# board2corrected.net
KiCad netlist of a schematic drawn in EAGLE
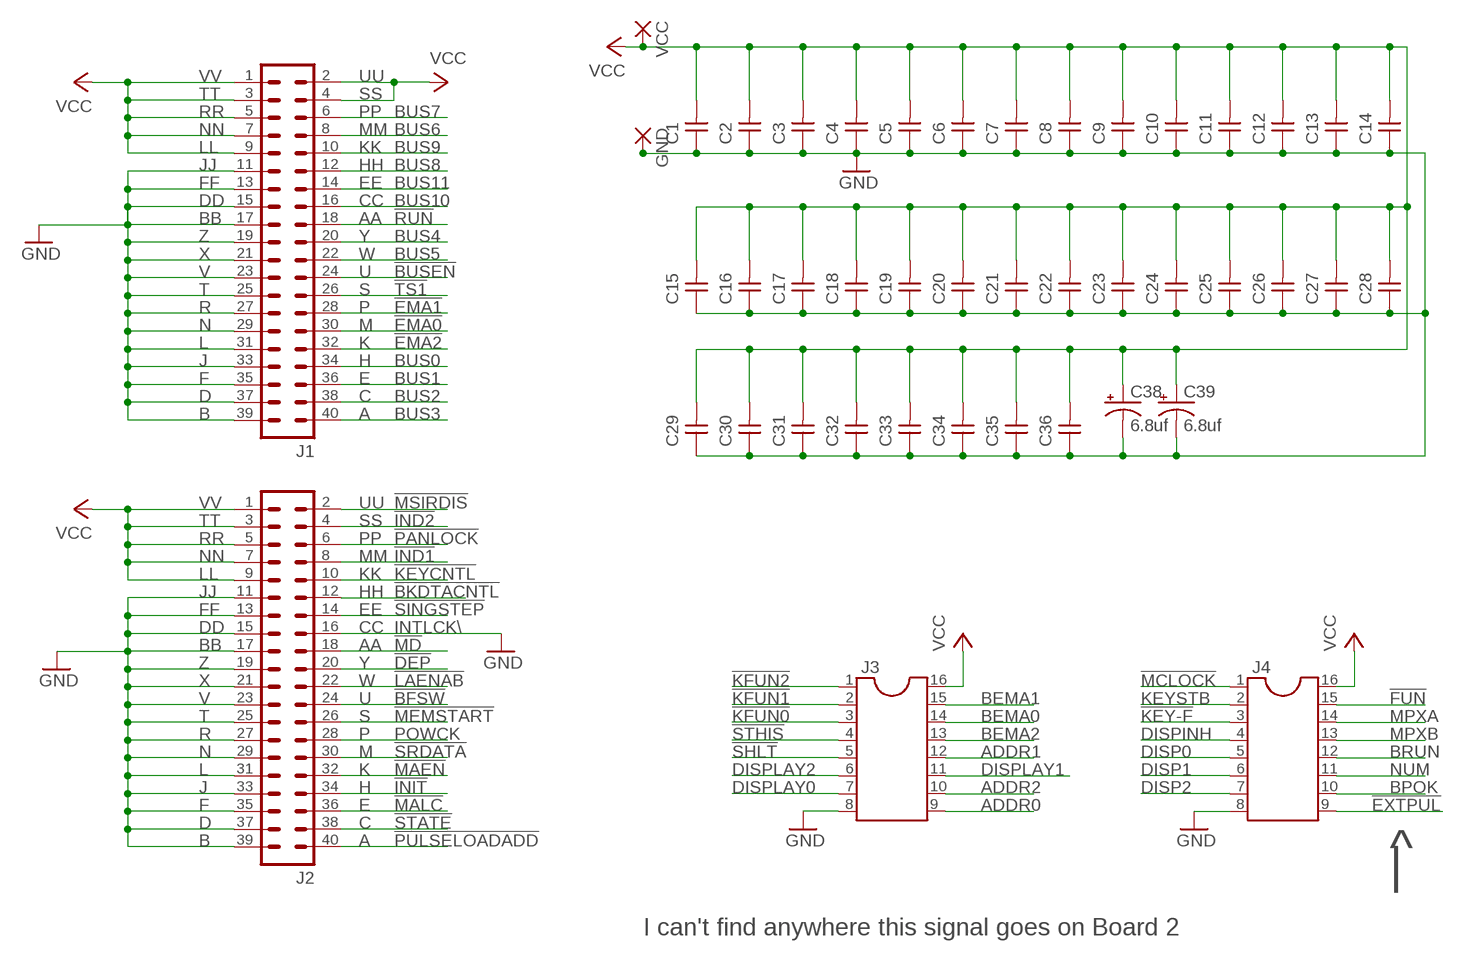
[diagram p0: schematic, sheet 1]
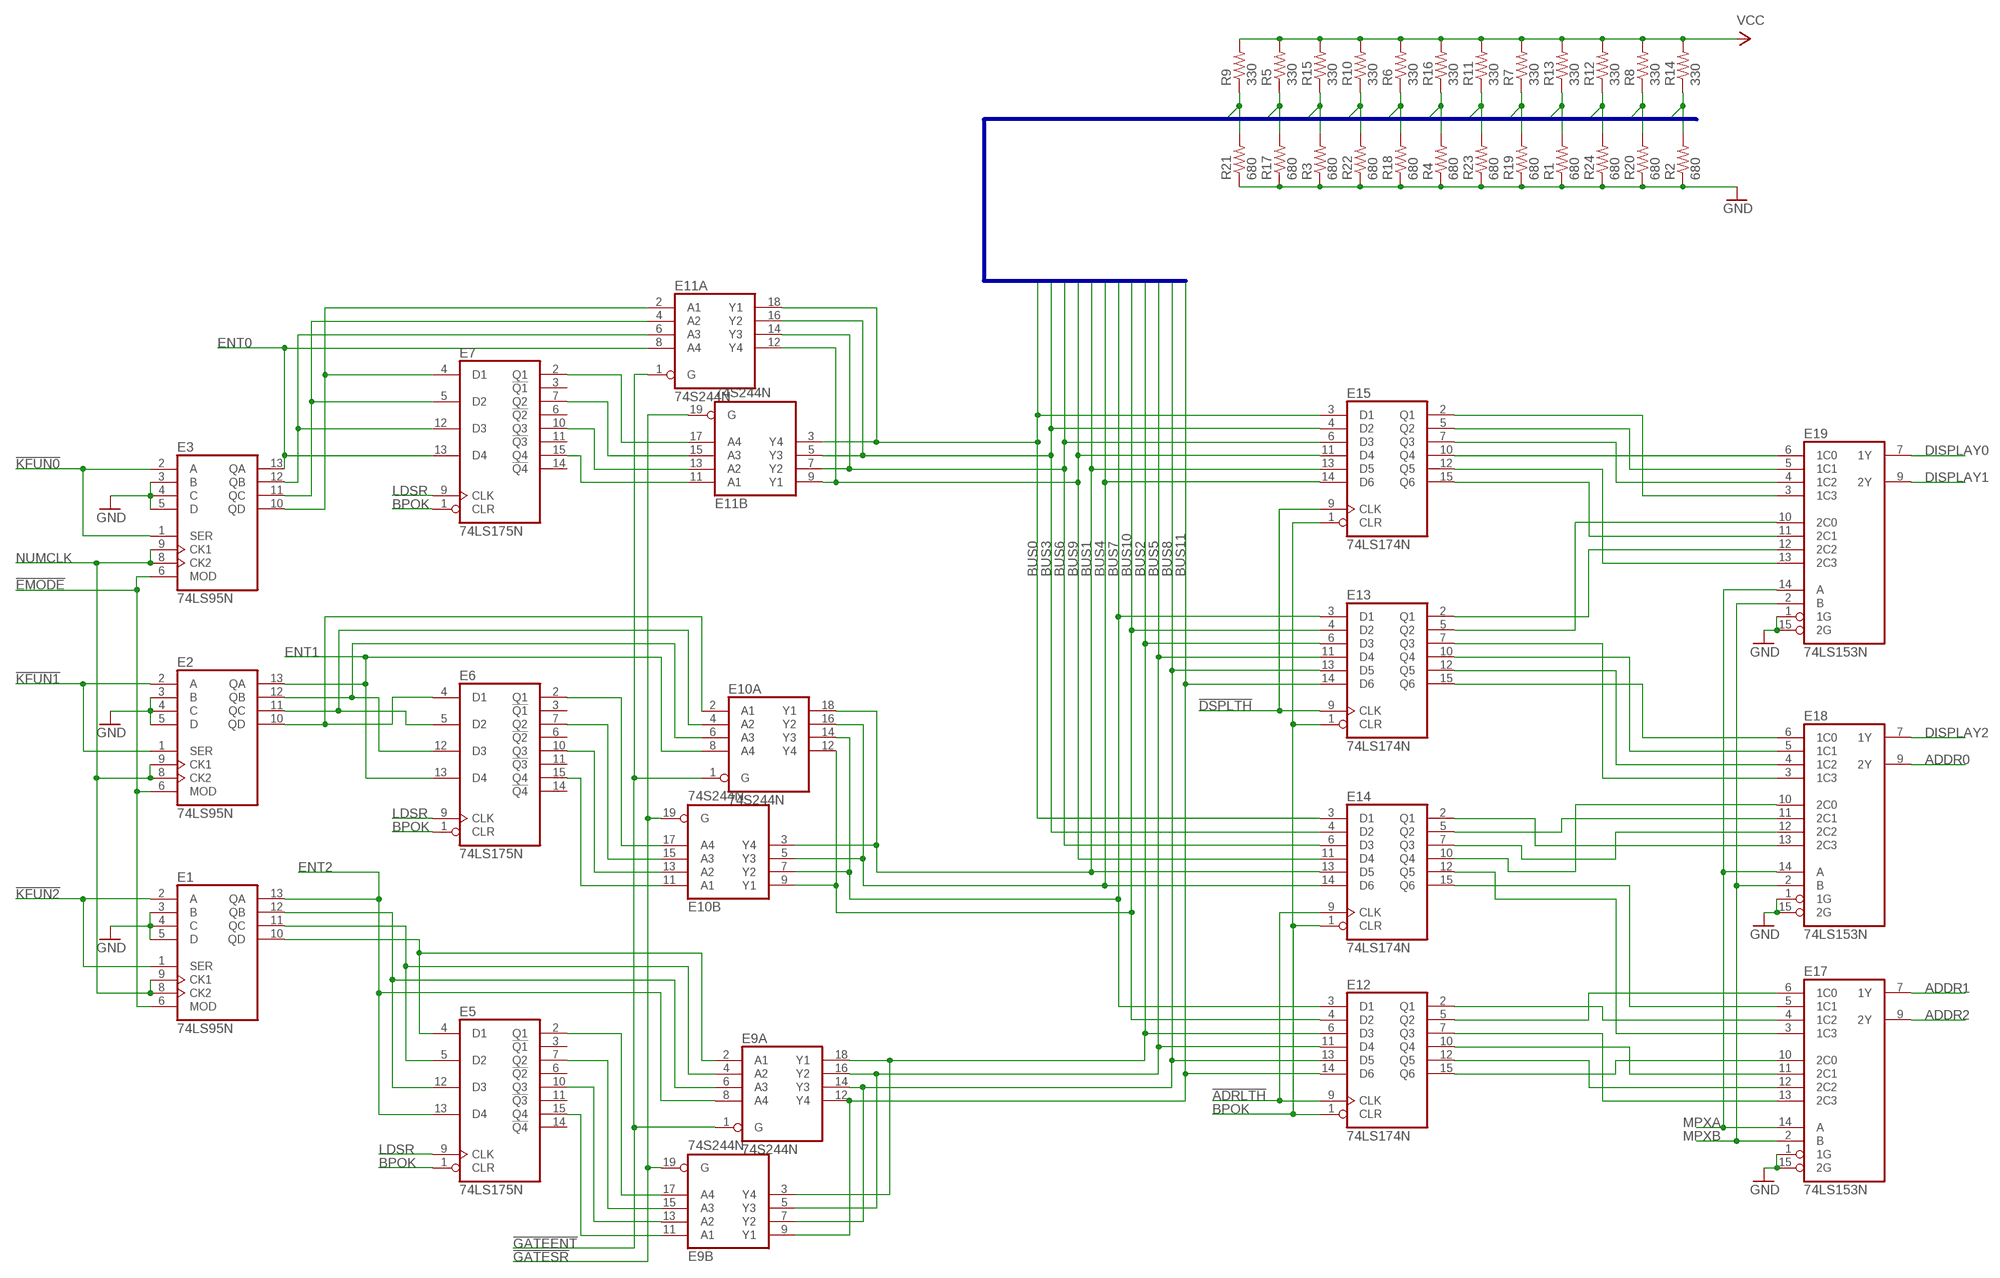
[diagram p1: schematic, sheet 2]
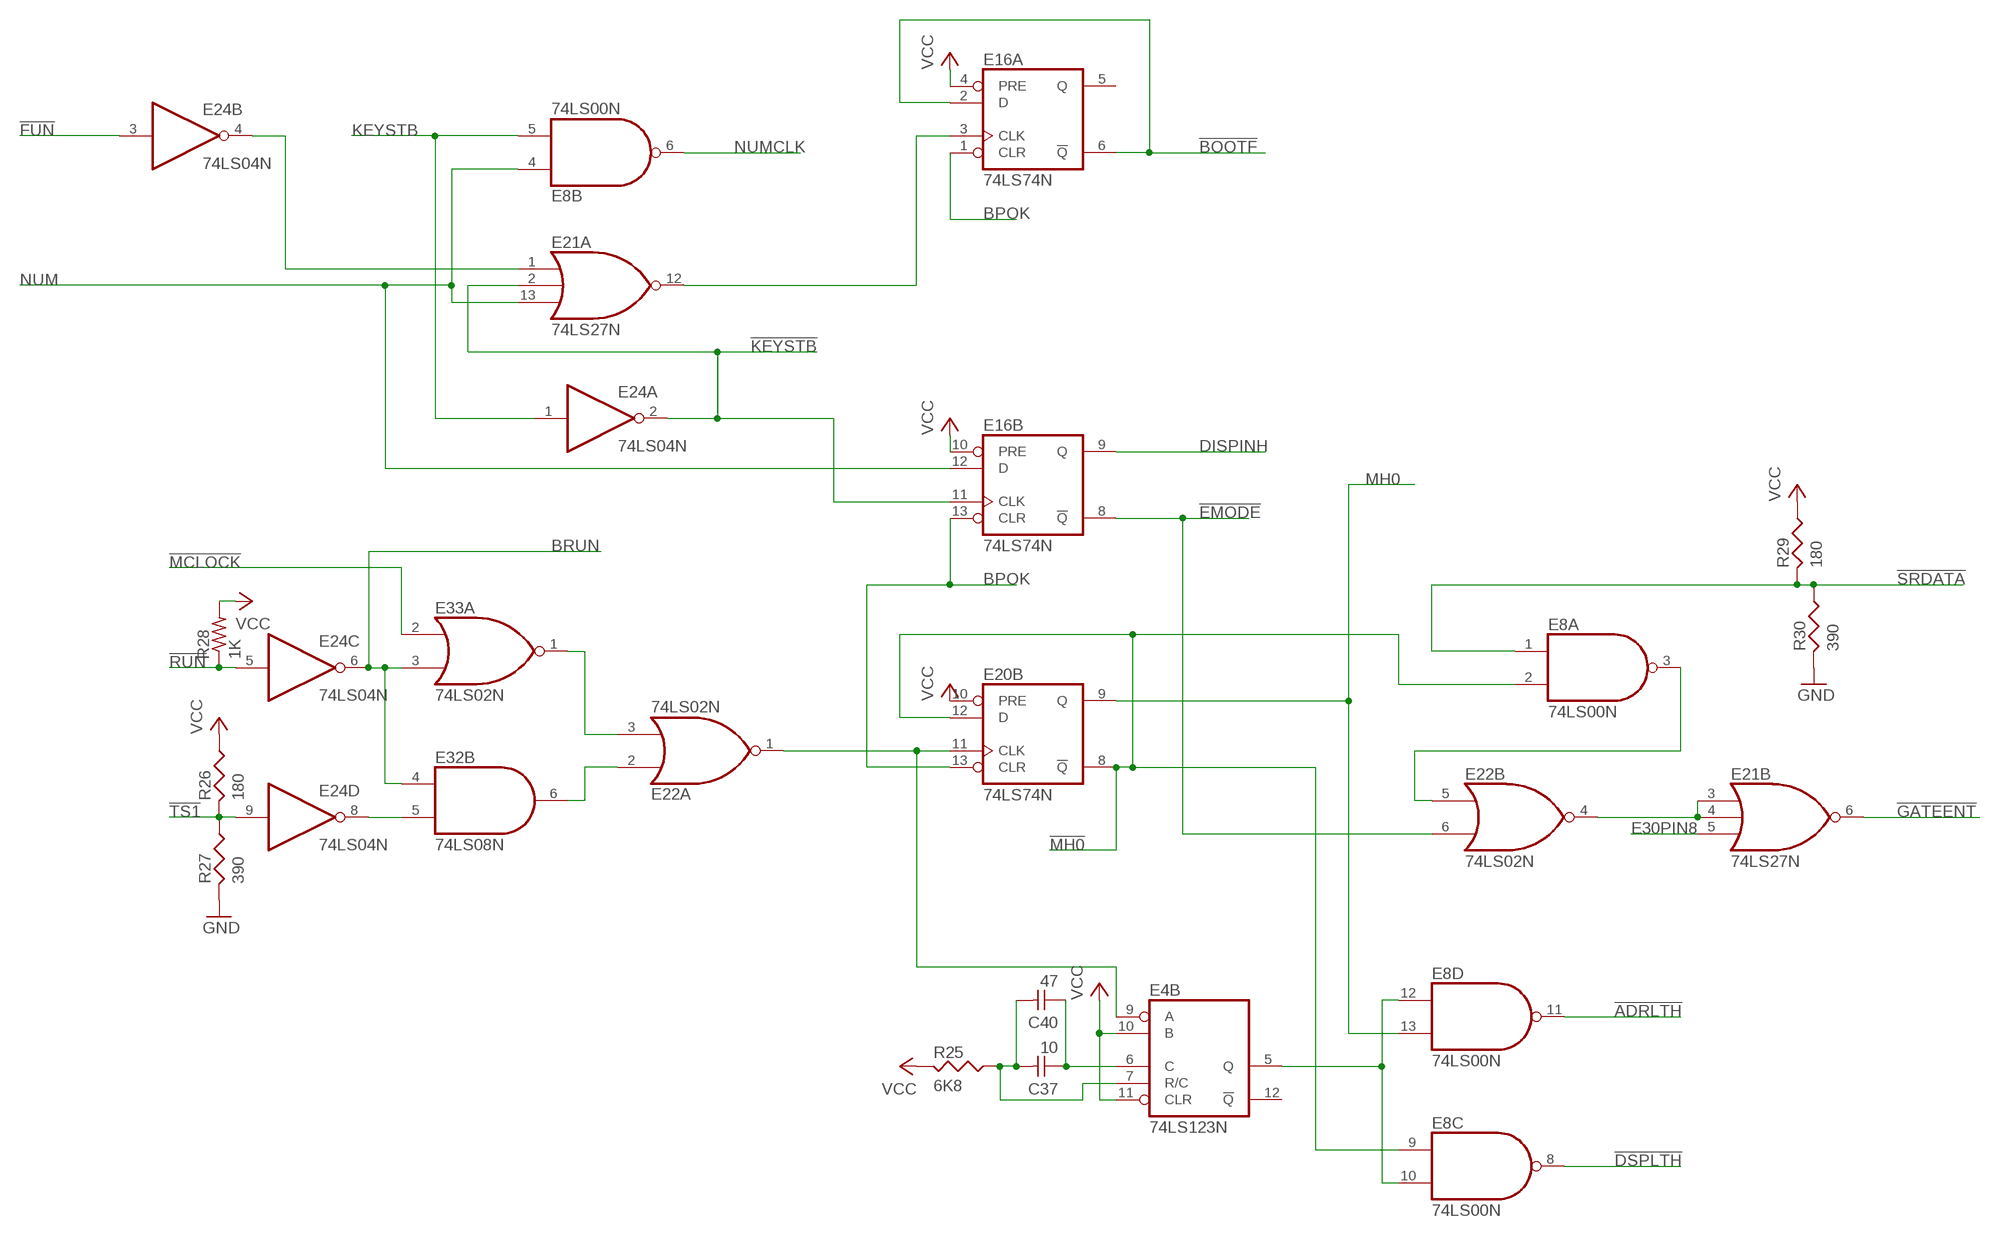
[diagram p2: schematic, sheet 3]
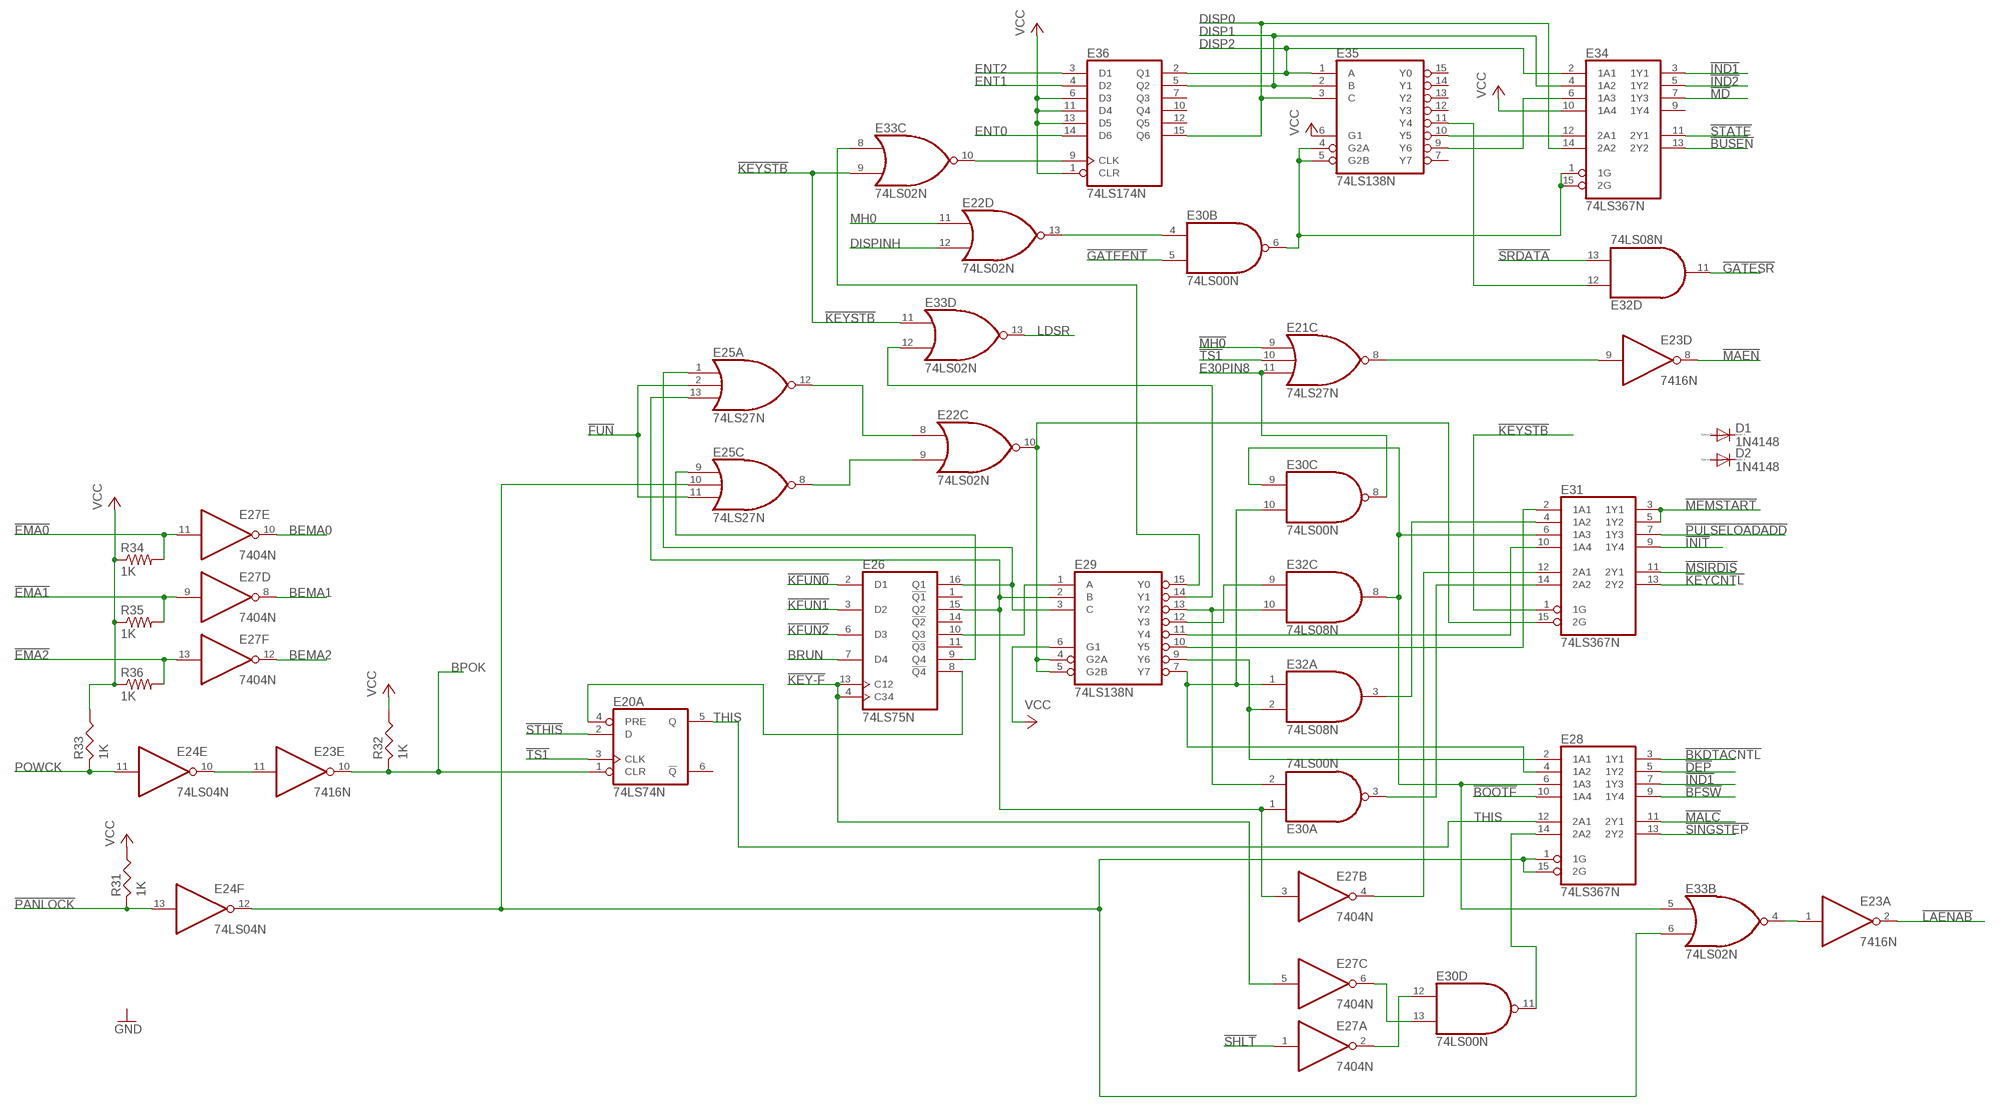
[diagram p3: schematic, sheet 4]

(export (version "E")
  (design (tool "Eeschema 10.0.6"))
  (components
    (comp (ref "D1")
      (value "1N4148")
      (footprint "eagle-import:DO35-10")
      (libsource (lib "eagle-import") (part "1N4148DO35-10"))
    )
    (comp (ref "D2")
      (value "1N4148")
      (footprint "eagle-import:DO35-10")
      (libsource (lib "eagle-import") (part "1N4148DO35-10"))
    )
    (comp (ref "E20")
      (value "74LS74N")
      (footprint "eagle-import:DIL14")
      (libsource (lib "eagle-import") (part "7474NLS"))
    )
    (comp (ref "E21")
      (value "74LS27N")
      (footprint "eagle-import:DIL14")
      (libsource (lib "eagle-import") (part "7427NLS"))
    )
    (comp (ref "E22")
      (value "74LS02N")
      (footprint "eagle-import:DIL14")
      (libsource (lib "eagle-import") (part "7402NLS"))
    )
    (comp (ref "E23")
      (value "7416N")
      (footprint "eagle-import:DIL14")
      (libsource (lib "eagle-import") (part "7416N"))
    )
    (comp (ref "E24")
      (value "74LS04N")
      (footprint "eagle-import:DIL14")
      (libsource (lib "eagle-import") (part "7404NLS"))
    )
    (comp (ref "E25")
      (value "74LS27N")
      (footprint "eagle-import:DIL14")
      (libsource (lib "eagle-import") (part "7427NLS"))
    )
    (comp (ref "E26")
      (value "74LS75N")
      (footprint "eagle-import:DIL16")
      (libsource (lib "eagle-import") (part "7475NLS"))
    )
    (comp (ref "E27")
      (value "7404N")
      (footprint "eagle-import:DIL14")
      (libsource (lib "eagle-import") (part "7404N"))
    )
    (comp (ref "E28")
      (value "74LS367N")
      (footprint "eagle-import:DIL16")
      (libsource (lib "eagle-import") (part "74367N"))
    )
    (comp (ref "E29")
      (value "74LS138N")
      (footprint "eagle-import:DIL16")
      (libsource (lib "eagle-import") (part "74138NLS"))
    )
    (comp (ref "E30")
      (value "74LS00N")
      (footprint "eagle-import:DIL14")
      (libsource (lib "eagle-import") (part "7400NLS"))
    )
    (comp (ref "E31")
      (value "74LS367N")
      (footprint "eagle-import:DIL16")
      (libsource (lib "eagle-import") (part "74367N"))
    )
    (comp (ref "E32")
      (value "74LS08N")
      (footprint "eagle-import:DIL14")
      (libsource (lib "eagle-import") (part "7408NLS"))
    )
    (comp (ref "E33")
      (value "74LS02N")
      (footprint "eagle-import:DIL14")
      (libsource (lib "eagle-import") (part "7402NLS"))
    )
    (comp (ref "E34")
      (value "74LS367N")
      (footprint "eagle-import:DIL16")
      (libsource (lib "eagle-import") (part "74367N"))
    )
    (comp (ref "E35")
      (value "74LS138N")
      (footprint "eagle-import:DIL16")
      (libsource (lib "eagle-import") (part "74138NLS"))
    )
    (comp (ref "E36")
      (value "74LS174N")
      (footprint "eagle-import:DIL16")
      (libsource (lib "eagle-import") (part "74174NLS"))
    )
    (comp (ref "R31")
      (value "1K")
      (footprint "eagle-import:R-10")
      (libsource (lib "eagle-import") (part "RESUS-10"))
    )
    (comp (ref "R32")
      (value "1K")
      (footprint "eagle-import:R-10")
      (libsource (lib "eagle-import") (part "RESUS-10"))
    )
    (comp (ref "R33")
      (value "1K")
      (footprint "eagle-import:R-10")
      (libsource (lib "eagle-import") (part "RESUS-10"))
    )
    (comp (ref "R34")
      (value "1K")
      (footprint "eagle-import:0207_10")
      (libsource (lib "eagle-import") (part "R-US_0207/10"))
    )
    (comp (ref "R35")
      (value "1K")
      (footprint "eagle-import:0207_10")
      (libsource (lib "eagle-import") (part "R-US_0207/10"))
    )
    (comp (ref "R36")
      (value "1K")
      (footprint "eagle-import:0207_10")
      (libsource (lib "eagle-import") (part "R-US_0207/10"))
    )
    (comp (ref "C1")
      (value "CAPNP-5")
      (footprint "eagle-import:C-5")
      (libsource (lib "eagle-import") (part "CAPNP-5"))
    )
    (comp (ref "C2")
      (value "CAPNP-5")
      (footprint "eagle-import:C-5")
      (libsource (lib "eagle-import") (part "CAPNP-5"))
    )
    (comp (ref "C3")
      (value "CAPNP-5")
      (footprint "eagle-import:C-5")
      (libsource (lib "eagle-import") (part "CAPNP-5"))
    )
    (comp (ref "C4")
      (value "CAPNP-5")
      (footprint "eagle-import:C-5")
      (libsource (lib "eagle-import") (part "CAPNP-5"))
    )
    (comp (ref "C5")
      (value "CAPNP-5")
      (footprint "eagle-import:C-5")
      (libsource (lib "eagle-import") (part "CAPNP-5"))
    )
    (comp (ref "C6")
      (value "CAPNP-5")
      (footprint "eagle-import:C-5")
      (libsource (lib "eagle-import") (part "CAPNP-5"))
    )
    (comp (ref "C7")
      (value "CAPNP-5")
      (footprint "eagle-import:C-5")
      (libsource (lib "eagle-import") (part "CAPNP-5"))
    )
    (comp (ref "C8")
      (value "CAPNP-5")
      (footprint "eagle-import:C-5")
      (libsource (lib "eagle-import") (part "CAPNP-5"))
    )
    (comp (ref "C9")
      (value "CAPNP-5")
      (footprint "eagle-import:C-5")
      (libsource (lib "eagle-import") (part "CAPNP-5"))
    )
    (comp (ref "C10")
      (value "CAPNP-5")
      (footprint "eagle-import:C-5")
      (libsource (lib "eagle-import") (part "CAPNP-5"))
    )
    (comp (ref "C11")
      (value "CAPNP-5")
      (footprint "eagle-import:C-5")
      (libsource (lib "eagle-import") (part "CAPNP-5"))
    )
    (comp (ref "C12")
      (value "CAPNP-5")
      (footprint "eagle-import:C-5")
      (libsource (lib "eagle-import") (part "CAPNP-5"))
    )
    (comp (ref "C13")
      (value "CAPNP-5")
      (footprint "eagle-import:C-5")
      (libsource (lib "eagle-import") (part "CAPNP-5"))
    )
    (comp (ref "C14")
      (value "CAPNP-5")
      (footprint "eagle-import:C-5")
      (libsource (lib "eagle-import") (part "CAPNP-5"))
    )
    (comp (ref "C15")
      (value "CAPNP-5")
      (footprint "eagle-import:C-5")
      (libsource (lib "eagle-import") (part "CAPNP-5"))
    )
    (comp (ref "C16")
      (value "CAPNP-5")
      (footprint "eagle-import:C-5")
      (libsource (lib "eagle-import") (part "CAPNP-5"))
    )
    (comp (ref "C17")
      (value "CAPNP-5")
      (footprint "eagle-import:C-5")
      (libsource (lib "eagle-import") (part "CAPNP-5"))
    )
    (comp (ref "C18")
      (value "CAPNP-5")
      (footprint "eagle-import:C-5")
      (libsource (lib "eagle-import") (part "CAPNP-5"))
    )
    (comp (ref "C19")
      (value "CAPNP-5")
      (footprint "eagle-import:C-5")
      (libsource (lib "eagle-import") (part "CAPNP-5"))
    )
    (comp (ref "C20")
      (value "CAPNP-5")
      (footprint "eagle-import:C-5")
      (libsource (lib "eagle-import") (part "CAPNP-5"))
    )
    (comp (ref "C21")
      (value "CAPNP-5")
      (footprint "eagle-import:C-5")
      (libsource (lib "eagle-import") (part "CAPNP-5"))
    )
    (comp (ref "C22")
      (value "CAPNP-5")
      (footprint "eagle-import:C-5")
      (libsource (lib "eagle-import") (part "CAPNP-5"))
    )
    (comp (ref "C23")
      (value "CAPNP-5")
      (footprint "eagle-import:C-5")
      (libsource (lib "eagle-import") (part "CAPNP-5"))
    )
    (comp (ref "C24")
      (value "CAPNP-5")
      (footprint "eagle-import:C-5")
      (libsource (lib "eagle-import") (part "CAPNP-5"))
    )
    (comp (ref "C25")
      (value "CAPNP-5")
      (footprint "eagle-import:C-5")
      (libsource (lib "eagle-import") (part "CAPNP-5"))
    )
    (comp (ref "C26")
      (value "CAPNP-5")
      (footprint "eagle-import:C-5")
      (libsource (lib "eagle-import") (part "CAPNP-5"))
    )
    (comp (ref "C27")
      (value "CAPNP-5")
      (footprint "eagle-import:C-5")
      (libsource (lib "eagle-import") (part "CAPNP-5"))
    )
    (comp (ref "C28")
      (value "CAPNP-5")
      (footprint "eagle-import:C-5")
      (libsource (lib "eagle-import") (part "CAPNP-5"))
    )
    (comp (ref "C29")
      (value "CAPNP-5")
      (footprint "eagle-import:C-5")
      (libsource (lib "eagle-import") (part "CAPNP-5"))
    )
    (comp (ref "C30")
      (value "CAPNP-5")
      (footprint "eagle-import:C-5")
      (libsource (lib "eagle-import") (part "CAPNP-5"))
    )
    (comp (ref "C31")
      (value "CAPNP-5")
      (footprint "eagle-import:C-5")
      (libsource (lib "eagle-import") (part "CAPNP-5"))
    )
    (comp (ref "C32")
      (value "CAPNP-5")
      (footprint "eagle-import:C-5")
      (libsource (lib "eagle-import") (part "CAPNP-5"))
    )
    (comp (ref "C33")
      (value "CAPNP-5")
      (footprint "eagle-import:C-5")
      (libsource (lib "eagle-import") (part "CAPNP-5"))
    )
    (comp (ref "C34")
      (value "CAPNP-5")
      (footprint "eagle-import:C-5")
      (libsource (lib "eagle-import") (part "CAPNP-5"))
    )
    (comp (ref "C35")
      (value "CAPNP-5")
      (footprint "eagle-import:C-5")
      (libsource (lib "eagle-import") (part "CAPNP-5"))
    )
    (comp (ref "C36")
      (value "CAPNP-5")
      (footprint "eagle-import:C-5")
      (libsource (lib "eagle-import") (part "CAPNP-5"))
    )
    (comp (ref "C38")
      (value "6.8uf")
      (footprint "eagle-import:E15-5")
      (libsource (lib "eagle-import") (part "CPOL-USE15-5AXIAL"))
    )
    (comp (ref "C39")
      (value "6.8uf")
      (footprint "eagle-import:E15-5")
      (libsource (lib "eagle-import") (part "CPOL-USE15-5AXIAL"))
    )
    (comp (ref "GND")
      (value "3,81/1,4")
      (footprint "eagle-import:3,81_1,4")
      (libsource (lib "eagle-import") (part "3,81/1,4"))
    )
    (comp (ref "J1")
      (value "40H")
      (footprint "eagle-import:40H")
      (libsource (lib "eagle-import") (part "40H"))
    )
    (comp (ref "J2")
      (value "40H")
      (footprint "eagle-import:40H")
      (libsource (lib "eagle-import") (part "40H"))
    )
    (comp (ref "J3")
      (value "DIL16S")
      (footprint "eagle-import:SOCKET-16")
      (libsource (lib "eagle-import") (part "DIL16S"))
    )
    (comp (ref "J4")
      (value "DIL16S")
      (footprint "eagle-import:SOCKET-16")
      (libsource (lib "eagle-import") (part "DIL16S"))
    )
    (comp (ref "VCC")
      (value "3,81/1,4")
      (footprint "eagle-import:3,81_1,4")
      (libsource (lib "eagle-import") (part "3,81/1,4"))
    )
    (comp (ref "E1")
      (value "74LS95N")
      (footprint "eagle-import:DIL14")
      (libsource (lib "eagle-import") (part "7495NLS"))
    )
    (comp (ref "E2")
      (value "74LS95N")
      (footprint "eagle-import:DIL14")
      (libsource (lib "eagle-import") (part "7495NLS"))
    )
    (comp (ref "E3")
      (value "74LS95N")
      (footprint "eagle-import:DIL14")
      (libsource (lib "eagle-import") (part "7495NLS"))
    )
    (comp (ref "E5")
      (value "74LS175N")
      (footprint "eagle-import:DIL16")
      (libsource (lib "eagle-import") (part "74175NLS"))
    )
    (comp (ref "E6")
      (value "74LS175N")
      (footprint "eagle-import:DIL16")
      (libsource (lib "eagle-import") (part "74175NLS"))
    )
    (comp (ref "E7")
      (value "74LS175N")
      (footprint "eagle-import:DIL16")
      (libsource (lib "eagle-import") (part "74175NLS"))
    )
    (comp (ref "E9")
      (value "74S244N")
      (footprint "eagle-import:DIL20")
      (libsource (lib "eagle-import") (part "74244NS"))
    )
    (comp (ref "E10")
      (value "74S244N")
      (footprint "eagle-import:DIL20")
      (libsource (lib "eagle-import") (part "74244NS"))
    )
    (comp (ref "E11")
      (value "74S244N")
      (footprint "eagle-import:DIL20")
      (libsource (lib "eagle-import") (part "74244NS"))
    )
    (comp (ref "E12")
      (value "74LS174N")
      (footprint "eagle-import:DIL16")
      (libsource (lib "eagle-import") (part "74174NLS"))
    )
    (comp (ref "E13")
      (value "74LS174N")
      (footprint "eagle-import:DIL16")
      (libsource (lib "eagle-import") (part "74174NLS"))
    )
    (comp (ref "E14")
      (value "74LS174N")
      (footprint "eagle-import:DIL16")
      (libsource (lib "eagle-import") (part "74174NLS"))
    )
    (comp (ref "E15")
      (value "74LS174N")
      (footprint "eagle-import:DIL16")
      (libsource (lib "eagle-import") (part "74174NLS"))
    )
    (comp (ref "E17")
      (value "74LS153N")
      (footprint "eagle-import:DIL16")
      (libsource (lib "eagle-import") (part "74153NLS"))
    )
    (comp (ref "E18")
      (value "74LS153N")
      (footprint "eagle-import:DIL16")
      (libsource (lib "eagle-import") (part "74153NLS"))
    )
    (comp (ref "E19")
      (value "74LS153N")
      (footprint "eagle-import:DIL16")
      (libsource (lib "eagle-import") (part "74153NLS"))
    )
    (comp (ref "R1")
      (value "680")
      (footprint "eagle-import:0207_10")
      (libsource (lib "eagle-import") (part "R-US_0207/10"))
    )
    (comp (ref "R2")
      (value "680")
      (footprint "eagle-import:0207_10")
      (libsource (lib "eagle-import") (part "R-US_0207/10"))
    )
    (comp (ref "R3")
      (value "680")
      (footprint "eagle-import:0207_10")
      (libsource (lib "eagle-import") (part "R-US_0207/10"))
    )
    (comp (ref "R4")
      (value "680")
      (footprint "eagle-import:0207_10")
      (libsource (lib "eagle-import") (part "R-US_0207/10"))
    )
    (comp (ref "R5")
      (value "330")
      (footprint "eagle-import:0207_10")
      (libsource (lib "eagle-import") (part "R-US_0207/10"))
    )
    (comp (ref "R6")
      (value "330")
      (footprint "eagle-import:0207_10")
      (libsource (lib "eagle-import") (part "R-US_0207/10"))
    )
    (comp (ref "R7")
      (value "330")
      (footprint "eagle-import:0207_10")
      (libsource (lib "eagle-import") (part "R-US_0207/10"))
    )
    (comp (ref "R8")
      (value "330")
      (footprint "eagle-import:0207_10")
      (libsource (lib "eagle-import") (part "R-US_0207/10"))
    )
    (comp (ref "R9")
      (value "330")
      (footprint "eagle-import:0207_10")
      (libsource (lib "eagle-import") (part "R-US_0207/10"))
    )
    (comp (ref "R10")
      (value "330")
      (footprint "eagle-import:0207_10")
      (libsource (lib "eagle-import") (part "R-US_0207/10"))
    )
    (comp (ref "R11")
      (value "330")
      (footprint "eagle-import:0207_10")
      (libsource (lib "eagle-import") (part "R-US_0207/10"))
    )
    (comp (ref "R12")
      (value "330")
      (footprint "eagle-import:0207_10")
      (libsource (lib "eagle-import") (part "R-US_0207/10"))
    )
    (comp (ref "R13")
      (value "330")
      (footprint "eagle-import:0207_10")
      (libsource (lib "eagle-import") (part "R-US_0207/10"))
    )
    (comp (ref "R14")
      (value "330")
      (footprint "eagle-import:0207_10")
      (libsource (lib "eagle-import") (part "R-US_0207/10"))
    )
    (comp (ref "R15")
      (value "330")
      (footprint "eagle-import:0207_10")
      (libsource (lib "eagle-import") (part "R-US_0207/10"))
    )
    (comp (ref "R16")
      (value "330")
      (footprint "eagle-import:0207_10")
      (libsource (lib "eagle-import") (part "R-US_0207/10"))
    )
    (comp (ref "R17")
      (value "680")
      (footprint "eagle-import:0207_10")
      (libsource (lib "eagle-import") (part "R-US_0207/10"))
    )
    (comp (ref "R18")
      (value "680")
      (footprint "eagle-import:0207_10")
      (libsource (lib "eagle-import") (part "R-US_0207/10"))
    )
    (comp (ref "R19")
      (value "680")
      (footprint "eagle-import:0207_10")
      (libsource (lib "eagle-import") (part "R-US_0207/10"))
    )
    (comp (ref "R20")
      (value "680")
      (footprint "eagle-import:0207_10")
      (libsource (lib "eagle-import") (part "R-US_0207/10"))
    )
    (comp (ref "R21")
      (value "680")
      (footprint "eagle-import:0207_10")
      (libsource (lib "eagle-import") (part "R-US_0207/10"))
    )
    (comp (ref "R22")
      (value "680")
      (footprint "eagle-import:0207_10")
      (libsource (lib "eagle-import") (part "R-US_0207/10"))
    )
    (comp (ref "R23")
      (value "680")
      (footprint "eagle-import:0207_10")
      (libsource (lib "eagle-import") (part "R-US_0207/10"))
    )
    (comp (ref "R24")
      (value "680")
      (footprint "eagle-import:0207_10")
      (libsource (lib "eagle-import") (part "R-US_0207/10"))
    )
    (comp (ref "C37")
      (value "10")
      (footprint "eagle-import:C-5")
      (libsource (lib "eagle-import") (part "CAPNP-5"))
    )
    (comp (ref "C40")
      (value "47")
      (footprint "eagle-import:C-5")
      (libsource (lib "eagle-import") (part "CAPNP-5"))
    )
    (comp (ref "E4")
      (value "74LS123N")
      (footprint "eagle-import:DIL16")
      (libsource (lib "eagle-import") (part "74123NLS"))
    )
    (comp (ref "E8")
      (value "74LS00N")
      (footprint "eagle-import:DIL14")
      (libsource (lib "eagle-import") (part "7400NLS"))
    )
    (comp (ref "E16")
      (value "74LS74N")
      (footprint "eagle-import:DIL14")
      (libsource (lib "eagle-import") (part "7474NLS"))
    )
    (comp (ref "R25")
      (value "6K8")
      (footprint "eagle-import:R-10")
      (libsource (lib "eagle-import") (part "RESUS-10"))
    )
    (comp (ref "R26")
      (value "180")
      (footprint "eagle-import:R-10")
      (libsource (lib "eagle-import") (part "RESUS-10"))
    )
    (comp (ref "R27")
      (value "390")
      (footprint "eagle-import:R-10")
      (libsource (lib "eagle-import") (part "RESUS-10"))
    )
    (comp (ref "R28")
      (value "1K")
      (footprint "eagle-import:0207_10")
      (libsource (lib "eagle-import") (part "R-US_0207/10"))
    )
    (comp (ref "R29")
      (value "180")
      (footprint "eagle-import:R-10")
      (libsource (lib "eagle-import") (part "RESUS-10"))
    )
    (comp (ref "R30")
      (value "390")
      (footprint "eagle-import:R-10")
      (libsource (lib "eagle-import") (part "RESUS-10"))
    )
  )
  (nets
    (net (code "1") (name "ADDR0") (class "Default")
      (node (ref "E18") (pin "9") (pinfunction "2Y_9") (pintype "output"))
      (node (ref "J3") (pin "9") (pinfunction "9_9") (pintype "passive"))
    )
    (net (code "2") (name "ADDR1") (class "Default")
      (node (ref "E17") (pin "7") (pinfunction "1Y_7") (pintype "output"))
      (node (ref "J3") (pin "12") (pinfunction "12_12") (pintype "passive"))
    )
    (net (code "3") (name "ADDR2") (class "Default")
      (node (ref "E17") (pin "9") (pinfunction "2Y_9") (pintype "output"))
      (node (ref "J3") (pin "10") (pinfunction "10_10") (pintype "passive"))
    )
    (net (code "4") (name "BEMA0") (class "Default")
      (node (ref "E27") (pin "10") (pinfunction "O_10") (pintype "output"))
      (node (ref "J3") (pin "14") (pinfunction "14_14") (pintype "passive"))
    )
    (net (code "5") (name "BEMA1") (class "Default")
      (node (ref "E27") (pin "8") (pinfunction "O_8") (pintype "output"))
      (node (ref "J3") (pin "15") (pinfunction "15_15") (pintype "passive"))
    )
    (net (code "6") (name "BEMA2") (class "Default")
      (node (ref "E27") (pin "12") (pinfunction "O_12") (pintype "output"))
      (node (ref "J3") (pin "13") (pinfunction "13_13") (pintype "passive"))
    )
    (net (code "7") (name "BPOK") (class "Default")
      (node (ref "E12") (pin "1") (pinfunction "CLR_1") (pintype "input"))
      (node (ref "E13") (pin "1") (pinfunction "CLR_1") (pintype "input"))
      (node (ref "E14") (pin "1") (pinfunction "CLR_1") (pintype "input"))
      (node (ref "E15") (pin "1") (pinfunction "CLR_1") (pintype "input"))
      (node (ref "E16") (pin "1") (pinfunction "CLR_1") (pintype "input"))
      (node (ref "E16") (pin "13") (pinfunction "CLR_13") (pintype "input"))
      (node (ref "E20") (pin "1") (pinfunction "CLR_1") (pintype "input"))
      (node (ref "E20") (pin "13") (pinfunction "CLR_13") (pintype "input"))
      (node (ref "E23") (pin "10") (pinfunction "O_10") (pintype "open_collector"))
      (node (ref "E5") (pin "1") (pinfunction "CLR_1") (pintype "input"))
      (node (ref "E6") (pin "1") (pinfunction "CLR_1") (pintype "input"))
      (node (ref "E7") (pin "1") (pinfunction "CLR_1") (pintype "input"))
      (node (ref "J4") (pin "10") (pinfunction "10_10") (pintype "passive"))
      (node (ref "R32") (pin "2") (pinfunction "2_2") (pintype "passive"))
    )
    (net (code "8") (name "BRUN") (class "Default")
      (node (ref "E24") (pin "6") (pinfunction "O_6") (pintype "output"))
      (node (ref "E26") (pin "7") (pinfunction "D4_7") (pintype "input"))
      (node (ref "E32") (pin "4") (pinfunction "I0_4") (pintype "input"))
      (node (ref "E33") (pin "3") (pinfunction "I1_3") (pintype "input"))
      (node (ref "J4") (pin "12") (pinfunction "12_12") (pintype "passive"))
    )
    (net (code "9") (name "BUS0") (class "Default")
      (node (ref "E11") (pin "18") (pinfunction "Y1_18") (pintype "tri_state"))
      (node (ref "E11") (pin "3") (pinfunction "Y4_3") (pintype "tri_state"))
      (node (ref "E14") (pin "3") (pinfunction "D1_3") (pintype "input"))
      (node (ref "E15") (pin "3") (pinfunction "D1_3") (pintype "input"))
      (node (ref "J1") (pin "34") (pinfunction "34_34") (pintype "passive"))
      (node (ref "R21") (pin "2") (pinfunction "2_2") (pintype "passive"))
      (node (ref "R9") (pin "1") (pinfunction "1_1") (pintype "passive"))
    )
    (net (code "10") (name "BUS1") (class "Default")
      (node (ref "E10") (pin "18") (pinfunction "Y1_18") (pintype "tri_state"))
      (node (ref "E10") (pin "3") (pinfunction "Y4_3") (pintype "tri_state"))
      (node (ref "E14") (pin "13") (pinfunction "D5_13") (pintype "input"))
      (node (ref "E15") (pin "13") (pinfunction "D5_13") (pintype "input"))
      (node (ref "J1") (pin "36") (pinfunction "36_36") (pintype "passive"))
      (node (ref "R17") (pin "2") (pinfunction "2_2") (pintype "passive"))
      (node (ref "R5") (pin "1") (pinfunction "1_1") (pintype "passive"))
    )
    (net (code "11") (name "BUS2") (class "Default")
      (node (ref "E12") (pin "6") (pinfunction "D3_6") (pintype "input"))
      (node (ref "E13") (pin "6") (pinfunction "D3_6") (pintype "input"))
      (node (ref "E9") (pin "18") (pinfunction "Y1_18") (pintype "tri_state"))
      (node (ref "E9") (pin "3") (pinfunction "Y4_3") (pintype "tri_state"))
      (node (ref "J1") (pin "38") (pinfunction "38_38") (pintype "passive"))
      (node (ref "R15") (pin "1") (pinfunction "1_1") (pintype "passive"))
      (node (ref "R3") (pin "2") (pinfunction "2_2") (pintype "passive"))
    )
    (net (code "12") (name "BUS3") (class "Default")
      (node (ref "E11") (pin "16") (pinfunction "Y2_16") (pintype "tri_state"))
      (node (ref "E11") (pin "5") (pinfunction "Y3_5") (pintype "tri_state"))
      (node (ref "E14") (pin "4") (pinfunction "D2_4") (pintype "input"))
      (node (ref "E15") (pin "4") (pinfunction "D2_4") (pintype "input"))
      (node (ref "J1") (pin "40") (pinfunction "40_40") (pintype "passive"))
      (node (ref "R10") (pin "1") (pinfunction "1_1") (pintype "passive"))
      (node (ref "R22") (pin "2") (pinfunction "2_2") (pintype "passive"))
    )
    (net (code "13") (name "BUS4") (class "Default")
      (node (ref "E10") (pin "16") (pinfunction "Y2_16") (pintype "tri_state"))
      (node (ref "E10") (pin "5") (pinfunction "Y3_5") (pintype "tri_state"))
      (node (ref "E14") (pin "14") (pinfunction "D6_14") (pintype "input"))
      (node (ref "E15") (pin "14") (pinfunction "D6_14") (pintype "input"))
      (node (ref "J1") (pin "20") (pinfunction "20_20") (pintype "passive"))
      (node (ref "R18") (pin "2") (pinfunction "2_2") (pintype "passive"))
      (node (ref "R6") (pin "1") (pinfunction "1_1") (pintype "passive"))
    )
    (net (code "14") (name "BUS5") (class "Default")
      (node (ref "E12") (pin "11") (pinfunction "D4_11") (pintype "input"))
      (node (ref "E13") (pin "11") (pinfunction "D4_11") (pintype "input"))
      (node (ref "E9") (pin "16") (pinfunction "Y2_16") (pintype "tri_state"))
      (node (ref "E9") (pin "5") (pinfunction "Y3_5") (pintype "tri_state"))
      (node (ref "J1") (pin "22") (pinfunction "22_22") (pintype "passive"))
      (node (ref "R16") (pin "1") (pinfunction "1_1") (pintype "passive"))
      (node (ref "R4") (pin "2") (pinfunction "2_2") (pintype "passive"))
    )
    (net (code "15") (name "BUS6") (class "Default")
      (node (ref "E11") (pin "14") (pinfunction "Y3_14") (pintype "tri_state"))
      (node (ref "E11") (pin "7") (pinfunction "Y2_7") (pintype "tri_state"))
      (node (ref "E14") (pin "6") (pinfunction "D3_6") (pintype "input"))
      (node (ref "E15") (pin "6") (pinfunction "D3_6") (pintype "input"))
      (node (ref "J1") (pin "8") (pinfunction "8_8") (pintype "passive"))
      (node (ref "R11") (pin "1") (pinfunction "1_1") (pintype "passive"))
      (node (ref "R23") (pin "2") (pinfunction "2_2") (pintype "passive"))
    )
    (net (code "16") (name "BUS7") (class "Default")
      (node (ref "E10") (pin "14") (pinfunction "Y3_14") (pintype "tri_state"))
      (node (ref "E10") (pin "7") (pinfunction "Y2_7") (pintype "tri_state"))
      (node (ref "E12") (pin "3") (pinfunction "D1_3") (pintype "input"))
      (node (ref "E13") (pin "3") (pinfunction "D1_3") (pintype "input"))
      (node (ref "J1") (pin "6") (pinfunction "6_6") (pintype "passive"))
      (node (ref "R19") (pin "2") (pinfunction "2_2") (pintype "passive"))
      (node (ref "R7") (pin "1") (pinfunction "1_1") (pintype "passive"))
    )
    (net (code "17") (name "BUS8") (class "Default")
      (node (ref "E12") (pin "13") (pinfunction "D5_13") (pintype "input"))
      (node (ref "E13") (pin "13") (pinfunction "D5_13") (pintype "input"))
      (node (ref "E9") (pin "14") (pinfunction "Y3_14") (pintype "tri_state"))
      (node (ref "E9") (pin "7") (pinfunction "Y2_7") (pintype "tri_state"))
      (node (ref "J1") (pin "12") (pinfunction "12_12") (pintype "passive"))
      (node (ref "R1") (pin "2") (pinfunction "2_2") (pintype "passive"))
      (node (ref "R12") (pin "1") (pinfunction "1_1") (pintype "passive"))
      (node (ref "R13") (pin "1") (pinfunction "1_1") (pintype "passive"))
      (node (ref "R24") (pin "2") (pinfunction "2_2") (pintype "passive"))
    )
    (net (code "18") (name "BUS9") (class "Default")
      (node (ref "E11") (pin "12") (pinfunction "Y4_12") (pintype "tri_state"))
      (node (ref "E11") (pin "9") (pinfunction "Y1_9") (pintype "tri_state"))
      (node (ref "E14") (pin "11") (pinfunction "D4_11") (pintype "input"))
      (node (ref "E15") (pin "11") (pinfunction "D4_11") (pintype "input"))
      (node (ref "J1") (pin "10") (pinfunction "10_10") (pintype "passive"))
    )
    (net (code "19") (name "BUS10") (class "Default")
      (node (ref "E10") (pin "12") (pinfunction "Y4_12") (pintype "tri_state"))
      (node (ref "E10") (pin "9") (pinfunction "Y1_9") (pintype "tri_state"))
      (node (ref "E12") (pin "4") (pinfunction "D2_4") (pintype "input"))
      (node (ref "E13") (pin "4") (pinfunction "D2_4") (pintype "input"))
      (node (ref "J1") (pin "16") (pinfunction "16_16") (pintype "passive"))
      (node (ref "R20") (pin "2") (pinfunction "2_2") (pintype "passive"))
      (node (ref "R8") (pin "1") (pinfunction "1_1") (pintype "passive"))
    )
    (net (code "20") (name "BUS11") (class "Default")
      (node (ref "E12") (pin "14") (pinfunction "D6_14") (pintype "input"))
      (node (ref "E13") (pin "14") (pinfunction "D6_14") (pintype "input"))
      (node (ref "E9") (pin "12") (pinfunction "Y4_12") (pintype "tri_state"))
      (node (ref "E9") (pin "9") (pinfunction "Y1_9") (pintype "tri_state"))
      (node (ref "J1") (pin "14") (pinfunction "14_14") (pintype "passive"))
      (node (ref "R14") (pin "1") (pinfunction "1_1") (pintype "passive"))
      (node (ref "R2") (pin "2") (pinfunction "2_2") (pintype "passive"))
    )
    (net (code "21") (name "DISP0") (class "Default")
      (node (ref "E34") (pin "14") (pinfunction "2A2_14") (pintype "input"))
      (node (ref "E35") (pin "3") (pinfunction "C_3") (pintype "input"))
      (node (ref "E36") (pin "15") (pinfunction "Q6_15") (pintype "output"))
      (node (ref "J4") (pin "5") (pinfunction "5_5") (pintype "passive"))
    )
    (net (code "22") (name "DISP1") (class "Default")
      (node (ref "E34") (pin "4") (pinfunction "1A2_4") (pintype "input"))
      (node (ref "E35") (pin "2") (pinfunction "B_2") (pintype "input"))
      (node (ref "E36") (pin "5") (pinfunction "Q2_5") (pintype "output"))
      (node (ref "J4") (pin "6") (pinfunction "6_6") (pintype "passive"))
    )
    (net (code "23") (name "DISP2") (class "Default")
      (node (ref "E34") (pin "2") (pinfunction "1A1_2") (pintype "input"))
      (node (ref "E35") (pin "1") (pinfunction "A_1") (pintype "input"))
      (node (ref "E36") (pin "2") (pinfunction "Q1_2") (pintype "output"))
      (node (ref "J4") (pin "7") (pinfunction "7_7") (pintype "passive"))
    )
    (net (code "24") (name "DISPINH") (class "Default")
      (node (ref "E16") (pin "9") (pinfunction "Q_9") (pintype "output"))
      (node (ref "E22") (pin "12") (pinfunction "I1_12") (pintype "input"))
      (node (ref "J4") (pin "4") (pinfunction "4_4") (pintype "passive"))
    )
    (net (code "25") (name "DISPLAY0") (class "Default")
      (node (ref "E19") (pin "7") (pinfunction "1Y_7") (pintype "output"))
      (node (ref "J3") (pin "7") (pinfunction "7_7") (pintype "passive"))
    )
    (net (code "26") (name "DISPLAY1") (class "Default")
      (node (ref "E19") (pin "9") (pinfunction "2Y_9") (pintype "output"))
      (node (ref "J3") (pin "11") (pinfunction "11_11") (pintype "passive"))
    )
    (net (code "27") (name "DISPLAY2") (class "Default")
      (node (ref "E18") (pin "7") (pinfunction "1Y_7") (pintype "output"))
      (node (ref "J3") (pin "6") (pinfunction "6_6") (pintype "passive"))
    )
    (net (code "28") (name "E30PIN8") (class "Default")
      (node (ref "E21") (pin "11") (pinfunction "I2_11") (pintype "input"))
      (node (ref "E21") (pin "5") (pinfunction "I2_5") (pintype "input"))
      (node (ref "E30") (pin "8") (pinfunction "O_8") (pintype "output"))
    )
    (net (code "29") (name "ENT0") (class "Default")
      (node (ref "E11") (pin "8") (pinfunction "A4_8") (pintype "input"))
      (node (ref "E3") (pin "13") (pinfunction "QA_13") (pintype "output"))
      (node (ref "E36") (pin "14") (pinfunction "D6_14") (pintype "input"))
      (node (ref "E7") (pin "13") (pinfunction "D4_13") (pintype "input"))
    )
    (net (code "30") (name "ENT1") (class "Default")
      (node (ref "E10") (pin "8") (pinfunction "A4_8") (pintype "input"))
      (node (ref "E2") (pin "13") (pinfunction "QA_13") (pintype "output"))
      (node (ref "E36") (pin "4") (pinfunction "D2_4") (pintype "input"))
      (node (ref "E6") (pin "13") (pinfunction "D4_13") (pintype "input"))
    )
    (net (code "31") (name "ENT2") (class "Default")
      (node (ref "E1") (pin "13") (pinfunction "QA_13") (pintype "output"))
      (node (ref "E36") (pin "3") (pinfunction "D1_3") (pintype "input"))
      (node (ref "E5") (pin "13") (pinfunction "D4_13") (pintype "input"))
      (node (ref "E9") (pin "8") (pinfunction "A4_8") (pintype "input"))
    )
    (net (code "32") (name "GND") (class "Default")
      (node (ref "C1") (pin "1") (pinfunction "1_1") (pintype "passive"))
      (node (ref "C10") (pin "1") (pinfunction "1_1") (pintype "passive"))
      (node (ref "C11") (pin "1") (pinfunction "1_1") (pintype "passive"))
      (node (ref "C12") (pin "1") (pinfunction "1_1") (pintype "passive"))
      (node (ref "C13") (pin "1") (pinfunction "1_1") (pintype "passive"))
      (node (ref "C14") (pin "1") (pinfunction "1_1") (pintype "passive"))
      (node (ref "C15") (pin "1") (pinfunction "1_1") (pintype "passive"))
      (node (ref "C16") (pin "1") (pinfunction "1_1") (pintype "passive"))
      (node (ref "C17") (pin "1") (pinfunction "1_1") (pintype "passive"))
      (node (ref "C18") (pin "1") (pinfunction "1_1") (pintype "passive"))
      (node (ref "C19") (pin "1") (pinfunction "1_1") (pintype "passive"))
      (node (ref "C2") (pin "1") (pinfunction "1_1") (pintype "passive"))
      (node (ref "C20") (pin "1") (pinfunction "1_1") (pintype "passive"))
      (node (ref "C21") (pin "1") (pinfunction "1_1") (pintype "passive"))
      (node (ref "C22") (pin "1") (pinfunction "1_1") (pintype "passive"))
      (node (ref "C23") (pin "1") (pinfunction "1_1") (pintype "passive"))
      (node (ref "C24") (pin "1") (pinfunction "1_1") (pintype "passive"))
      (node (ref "C25") (pin "1") (pinfunction "1_1") (pintype "passive"))
      (node (ref "C26") (pin "1") (pinfunction "1_1") (pintype "passive"))
      (node (ref "C27") (pin "1") (pinfunction "1_1") (pintype "passive"))
      (node (ref "C28") (pin "1") (pinfunction "1_1") (pintype "passive"))
      (node (ref "C29") (pin "1") (pinfunction "1_1") (pintype "passive"))
      (node (ref "C3") (pin "1") (pinfunction "1_1") (pintype "passive"))
      (node (ref "C30") (pin "1") (pinfunction "1_1") (pintype "passive"))
      (node (ref "C31") (pin "1") (pinfunction "1_1") (pintype "passive"))
      (node (ref "C32") (pin "1") (pinfunction "1_1") (pintype "passive"))
      (node (ref "C33") (pin "1") (pinfunction "1_1") (pintype "passive"))
      (node (ref "C34") (pin "1") (pinfunction "1_1") (pintype "passive"))
      (node (ref "C35") (pin "1") (pinfunction "1_1") (pintype "passive"))
      (node (ref "C36") (pin "1") (pinfunction "1_1") (pintype "passive"))
      (node (ref "C38") (pin "-") (pinfunction "-_-") (pintype "passive"))
      (node (ref "C39") (pin "-") (pinfunction "-_-") (pintype "passive"))
      (node (ref "C4") (pin "1") (pinfunction "1_1") (pintype "passive"))
      (node (ref "C5") (pin "1") (pinfunction "1_1") (pintype "passive"))
      (node (ref "C6") (pin "1") (pinfunction "1_1") (pintype "passive"))
      (node (ref "C7") (pin "1") (pinfunction "1_1") (pintype "passive"))
      (node (ref "C8") (pin "1") (pinfunction "1_1") (pintype "passive"))
      (node (ref "C9") (pin "1") (pinfunction "1_1") (pintype "passive"))
      (node (ref "E1") (pin "3") (pinfunction "B_3") (pintype "input"))
      (node (ref "E1") (pin "4") (pinfunction "C_4") (pintype "input"))
      (node (ref "E1") (pin "5") (pinfunction "D_5") (pintype "input"))
      (node (ref "E17") (pin "1") (pinfunction "1G_1") (pintype "input"))
      (node (ref "E17") (pin "15") (pinfunction "2G_15") (pintype "input"))
      (node (ref "E18") (pin "1") (pinfunction "1G_1") (pintype "input"))
      (node (ref "E18") (pin "15") (pinfunction "2G_15") (pintype "input"))
      (node (ref "E19") (pin "1") (pinfunction "1G_1") (pintype "input"))
      (node (ref "E19") (pin "15") (pinfunction "2G_15") (pintype "input"))
      (node (ref "E2") (pin "3") (pinfunction "B_3") (pintype "input"))
      (node (ref "E2") (pin "4") (pinfunction "C_4") (pintype "input"))
      (node (ref "E2") (pin "5") (pinfunction "D_5") (pintype "input"))
      (node (ref "E3") (pin "3") (pinfunction "B_3") (pintype "input"))
      (node (ref "E3") (pin "4") (pinfunction "C_4") (pintype "input"))
      (node (ref "E3") (pin "5") (pinfunction "D_5") (pintype "input"))
      (node (ref "GND") (pin "1") (pinfunction "P_1") (pintype "passive"))
      (node (ref "J1") (pin "11") (pinfunction "11_11") (pintype "passive"))
      (node (ref "J1") (pin "13") (pinfunction "13_13") (pintype "passive"))
      (node (ref "J1") (pin "15") (pinfunction "15_15") (pintype "passive"))
      (node (ref "J1") (pin "17") (pinfunction "17_17") (pintype "passive"))
      (node (ref "J1") (pin "19") (pinfunction "19_19") (pintype "passive"))
      (node (ref "J1") (pin "21") (pinfunction "21_21") (pintype "passive"))
      (node (ref "J1") (pin "23") (pinfunction "23_23") (pintype "passive"))
      (node (ref "J1") (pin "25") (pinfunction "25_25") (pintype "passive"))
      (node (ref "J1") (pin "27") (pinfunction "27_27") (pintype "passive"))
      (node (ref "J1") (pin "29") (pinfunction "29_29") (pintype "passive"))
      (node (ref "J1") (pin "31") (pinfunction "31_31") (pintype "passive"))
      (node (ref "J1") (pin "33") (pinfunction "33_33") (pintype "passive"))
      (node (ref "J1") (pin "35") (pinfunction "35_35") (pintype "passive"))
      (node (ref "J1") (pin "37") (pinfunction "37_37") (pintype "passive"))
      (node (ref "J1") (pin "39") (pinfunction "39_39") (pintype "passive"))
      (node (ref "J2") (pin "11") (pinfunction "11_11") (pintype "passive"))
      (node (ref "J2") (pin "13") (pinfunction "13_13") (pintype "passive"))
      (node (ref "J2") (pin "15") (pinfunction "15_15") (pintype "passive"))
      (node (ref "J2") (pin "16") (pinfunction "16_16") (pintype "passive"))
      (node (ref "J2") (pin "17") (pinfunction "17_17") (pintype "passive"))
      (node (ref "J2") (pin "19") (pinfunction "19_19") (pintype "passive"))
      (node (ref "J2") (pin "21") (pinfunction "21_21") (pintype "passive"))
      (node (ref "J2") (pin "23") (pinfunction "23_23") (pintype "passive"))
      (node (ref "J2") (pin "25") (pinfunction "25_25") (pintype "passive"))
      (node (ref "J2") (pin "27") (pinfunction "27_27") (pintype "passive"))
      (node (ref "J2") (pin "29") (pinfunction "29_29") (pintype "passive"))
      (node (ref "J2") (pin "31") (pinfunction "31_31") (pintype "passive"))
      (node (ref "J2") (pin "33") (pinfunction "33_33") (pintype "passive"))
      (node (ref "J2") (pin "35") (pinfunction "35_35") (pintype "passive"))
      (node (ref "J2") (pin "37") (pinfunction "37_37") (pintype "passive"))
      (node (ref "J2") (pin "39") (pinfunction "39_39") (pintype "passive"))
      (node (ref "J3") (pin "8") (pinfunction "8_8") (pintype "passive"))
      (node (ref "J4") (pin "8") (pinfunction "8_8") (pintype "passive"))
      (node (ref "R1") (pin "1") (pinfunction "1_1") (pintype "passive"))
      (node (ref "R17") (pin "1") (pinfunction "1_1") (pintype "passive"))
      (node (ref "R18") (pin "1") (pinfunction "1_1") (pintype "passive"))
      (node (ref "R19") (pin "1") (pinfunction "1_1") (pintype "passive"))
      (node (ref "R2") (pin "1") (pinfunction "1_1") (pintype "passive"))
      (node (ref "R20") (pin "1") (pinfunction "1_1") (pintype "passive"))
      (node (ref "R21") (pin "1") (pinfunction "1_1") (pintype "passive"))
      (node (ref "R22") (pin "1") (pinfunction "1_1") (pintype "passive"))
      (node (ref "R23") (pin "1") (pinfunction "1_1") (pintype "passive"))
      (node (ref "R24") (pin "1") (pinfunction "1_1") (pintype "passive"))
      (node (ref "R27") (pin "2") (pinfunction "2_2") (pintype "passive"))
      (node (ref "R3") (pin "1") (pinfunction "1_1") (pintype "passive"))
      (node (ref "R30") (pin "2") (pinfunction "2_2") (pintype "passive"))
      (node (ref "R4") (pin "1") (pinfunction "1_1") (pintype "passive"))
    )
    (net (code "33") (name "KEYSTB") (class "Default")
      (node (ref "E24") (pin "1") (pinfunction "I_1") (pintype "input"))
      (node (ref "E8") (pin "5") (pinfunction "I1_5") (pintype "input"))
      (node (ref "J4") (pin "2") (pinfunction "2_2") (pintype "passive"))
    )
    (net (code "34") (name "LDSR") (class "Default")
      (node (ref "E33") (pin "13") (pinfunction "O_13") (pintype "output"))
      (node (ref "E5") (pin "9") (pinfunction "CLK_9") (pintype "input"))
      (node (ref "E6") (pin "9") (pinfunction "CLK_9") (pintype "input"))
      (node (ref "E7") (pin "9") (pinfunction "CLK_9") (pintype "input"))
    )
    (net (code "35") (name "MH0") (class "Default")
      (node (ref "E20") (pin "9") (pinfunction "Q_9") (pintype "output"))
      (node (ref "E22") (pin "11") (pinfunction "I0_11") (pintype "input"))
      (node (ref "E8") (pin "13") (pinfunction "I1_13") (pintype "input"))
    )
    (net (code "36") (name "MPXA") (class "Default")
      (node (ref "E17") (pin "14") (pinfunction "A_14") (pintype "input"))
      (node (ref "E18") (pin "14") (pinfunction "A_14") (pintype "input"))
      (node (ref "E19") (pin "14") (pinfunction "A_14") (pintype "input"))
      (node (ref "J4") (pin "14") (pinfunction "14_14") (pintype "passive"))
    )
    (net (code "37") (name "MPXB") (class "Default")
      (node (ref "E17") (pin "2") (pinfunction "B_2") (pintype "input"))
      (node (ref "E18") (pin "2") (pinfunction "B_2") (pintype "input"))
      (node (ref "E19") (pin "2") (pinfunction "B_2") (pintype "input"))
      (node (ref "J4") (pin "13") (pinfunction "13_13") (pintype "passive"))
    )
    (net (code "38") (name "NUM") (class "Default")
      (node (ref "E16") (pin "12") (pinfunction "D_12") (pintype "input"))
      (node (ref "E21") (pin "13") (pinfunction "I2_13") (pintype "input"))
      (node (ref "E8") (pin "4") (pinfunction "I0_4") (pintype "input"))
      (node (ref "J4") (pin "11") (pinfunction "11_11") (pintype "passive"))
    )
    (net (code "39") (name "NUMCLK") (class "Default")
      (node (ref "E1") (pin "8") (pinfunction "CK2_8") (pintype "input"))
      (node (ref "E1") (pin "9") (pinfunction "CK1_9") (pintype "input"))
      (node (ref "E2") (pin "8") (pinfunction "CK2_8") (pintype "input"))
      (node (ref "E2") (pin "9") (pinfunction "CK1_9") (pintype "input"))
      (node (ref "E3") (pin "8") (pinfunction "CK2_8") (pintype "input"))
      (node (ref "E3") (pin "9") (pinfunction "CK1_9") (pintype "input"))
      (node (ref "E8") (pin "6") (pinfunction "O_6") (pintype "output"))
    )
    (net (code "40") (name "Net-(E1A-QB)") (class "Default")
      (node (ref "E1") (pin "12") (pinfunction "QB_12") (pintype "output"))
      (node (ref "E5") (pin "12") (pinfunction "D3_12") (pintype "input"))
      (node (ref "E9") (pin "6") (pinfunction "A3_6") (pintype "input"))
    )
    (net (code "41") (name "Net-(E1A-QC)") (class "Default")
      (node (ref "E1") (pin "11") (pinfunction "QC_11") (pintype "output"))
      (node (ref "E5") (pin "5") (pinfunction "D2_5") (pintype "input"))
      (node (ref "E9") (pin "4") (pinfunction "A2_4") (pintype "input"))
    )
    (net (code "42") (name "Net-(E1A-QD)") (class "Default")
      (node (ref "E1") (pin "10") (pinfunction "QD_10") (pintype "output"))
      (node (ref "E5") (pin "4") (pinfunction "D1_4") (pintype "input"))
      (node (ref "E9") (pin "2") (pinfunction "A1_2") (pintype "input"))
    )
    (net (code "43") (name "Net-(E4B-C)") (class "Default")
      (node (ref "C37") (pin "1") (pinfunction "1_1") (pintype "passive"))
      (node (ref "C40") (pin "1") (pinfunction "1_1") (pintype "passive"))
      (node (ref "E4") (pin "6") (pinfunction "C_6") (pintype "input"))
    )
    (net (code "44") (name "Net-(E4B-Q)") (class "Default")
      (node (ref "E4") (pin "5") (pinfunction "Q_5") (pintype "output"))
      (node (ref "E8") (pin "10") (pinfunction "I1_10") (pintype "input"))
      (node (ref "E8") (pin "12") (pinfunction "I0_12") (pintype "input"))
    )
    (net (code "45") (name "Net-(E4B-R{slash}C)") (class "Default")
      (node (ref "C37") (pin "2") (pinfunction "2_2") (pintype "passive"))
      (node (ref "C40") (pin "2") (pinfunction "2_2") (pintype "passive"))
      (node (ref "E4") (pin "7") (pinfunction "R/C_7") (pintype "input"))
      (node (ref "R25") (pin "1") (pinfunction "1_1") (pintype "passive"))
    )
    (net (code "46") (name "Net-(E5A-Q1)") (class "Default")
      (node (ref "E5") (pin "2") (pinfunction "Q1_2") (pintype "output"))
      (node (ref "E9") (pin "17") (pinfunction "A4_17") (pintype "input"))
    )
    (net (code "47") (name "Net-(E5A-Q2)") (class "Default")
      (node (ref "E5") (pin "7") (pinfunction "Q2_7") (pintype "output"))
      (node (ref "E9") (pin "15") (pinfunction "A3_15") (pintype "input"))
    )
    (net (code "48") (name "Net-(E5A-Q3)") (class "Default")
      (node (ref "E5") (pin "10") (pinfunction "Q3_10") (pintype "output"))
      (node (ref "E9") (pin "13") (pinfunction "A2_13") (pintype "input"))
    )
    (net (code "49") (name "Net-(E5A-Q4)") (class "Default")
      (node (ref "E5") (pin "15") (pinfunction "Q4_15") (pintype "output"))
      (node (ref "E9") (pin "11") (pinfunction "A1_11") (pintype "input"))
    )
    (net (code "50") (name "Net-(E10A-A1)") (class "Default")
      (node (ref "E10") (pin "2") (pinfunction "A1_2") (pintype "input"))
      (node (ref "E2") (pin "10") (pinfunction "QD_10") (pintype "output"))
      (node (ref "E6") (pin "4") (pinfunction "D1_4") (pintype "input"))
    )
    (net (code "51") (name "Net-(E10A-A2)") (class "Default")
      (node (ref "E10") (pin "4") (pinfunction "A2_4") (pintype "input"))
      (node (ref "E2") (pin "11") (pinfunction "QC_11") (pintype "output"))
      (node (ref "E6") (pin "5") (pinfunction "D2_5") (pintype "input"))
    )
    (net (code "52") (name "Net-(E10A-A3)") (class "Default")
      (node (ref "E10") (pin "6") (pinfunction "A3_6") (pintype "input"))
      (node (ref "E2") (pin "12") (pinfunction "QB_12") (pintype "output"))
      (node (ref "E6") (pin "12") (pinfunction "D3_12") (pintype "input"))
    )
    (net (code "53") (name "Net-(E10B-A1)") (class "Default")
      (node (ref "E10") (pin "11") (pinfunction "A1_11") (pintype "input"))
      (node (ref "E6") (pin "15") (pinfunction "Q4_15") (pintype "output"))
    )
    (net (code "54") (name "Net-(E10B-A2)") (class "Default")
      (node (ref "E10") (pin "13") (pinfunction "A2_13") (pintype "input"))
      (node (ref "E6") (pin "10") (pinfunction "Q3_10") (pintype "output"))
    )
    (net (code "55") (name "Net-(E10B-A3)") (class "Default")
      (node (ref "E10") (pin "15") (pinfunction "A3_15") (pintype "input"))
      (node (ref "E6") (pin "7") (pinfunction "Q2_7") (pintype "output"))
    )
    (net (code "56") (name "Net-(E10B-A4)") (class "Default")
      (node (ref "E10") (pin "17") (pinfunction "A4_17") (pintype "input"))
      (node (ref "E6") (pin "2") (pinfunction "Q1_2") (pintype "output"))
    )
    (net (code "57") (name "Net-(E11A-A1)") (class "Default")
      (node (ref "E11") (pin "2") (pinfunction "A1_2") (pintype "input"))
      (node (ref "E3") (pin "10") (pinfunction "QD_10") (pintype "output"))
      (node (ref "E7") (pin "4") (pinfunction "D1_4") (pintype "input"))
    )
    (net (code "58") (name "Net-(E11A-A2)") (class "Default")
      (node (ref "E11") (pin "4") (pinfunction "A2_4") (pintype "input"))
      (node (ref "E3") (pin "11") (pinfunction "QC_11") (pintype "output"))
      (node (ref "E7") (pin "5") (pinfunction "D2_5") (pintype "input"))
    )
    (net (code "59") (name "Net-(E11A-A3)") (class "Default")
      (node (ref "E11") (pin "6") (pinfunction "A3_6") (pintype "input"))
      (node (ref "E3") (pin "12") (pinfunction "QB_12") (pintype "output"))
      (node (ref "E7") (pin "12") (pinfunction "D3_12") (pintype "input"))
    )
    (net (code "60") (name "Net-(E11B-A1)") (class "Default")
      (node (ref "E11") (pin "11") (pinfunction "A1_11") (pintype "input"))
      (node (ref "E7") (pin "15") (pinfunction "Q4_15") (pintype "output"))
    )
    (net (code "61") (name "Net-(E11B-A2)") (class "Default")
      (node (ref "E11") (pin "13") (pinfunction "A2_13") (pintype "input"))
      (node (ref "E7") (pin "10") (pinfunction "Q3_10") (pintype "output"))
    )
    (net (code "62") (name "Net-(E11B-A3)") (class "Default")
      (node (ref "E11") (pin "15") (pinfunction "A3_15") (pintype "input"))
      (node (ref "E7") (pin "7") (pinfunction "Q2_7") (pintype "output"))
    )
    (net (code "63") (name "Net-(E11B-A4)") (class "Default")
      (node (ref "E11") (pin "17") (pinfunction "A4_17") (pintype "input"))
      (node (ref "E7") (pin "2") (pinfunction "Q1_2") (pintype "output"))
    )
    (net (code "64") (name "Net-(E12A-Q1)") (class "Default")
      (node (ref "E12") (pin "2") (pinfunction "Q1_2") (pintype "output"))
      (node (ref "E17") (pin "4") (pinfunction "1C2_4") (pintype "input"))
    )
    (net (code "65") (name "Net-(E12A-Q2)") (class "Default")
      (node (ref "E12") (pin "5") (pinfunction "Q2_5") (pintype "output"))
      (node (ref "E17") (pin "6") (pinfunction "1C0_6") (pintype "input"))
    )
    (net (code "66") (name "Net-(E12A-Q3)") (class "Default")
      (node (ref "E12") (pin "7") (pinfunction "Q3_7") (pintype "output"))
      (node (ref "E17") (pin "13") (pinfunction "2C3_13") (pintype "input"))
    )
    (net (code "67") (name "Net-(E12A-Q4)") (class "Default")
      (node (ref "E12") (pin "10") (pinfunction "Q4_10") (pintype "output"))
      (node (ref "E17") (pin "11") (pinfunction "2C1_11") (pintype "input"))
    )
    (net (code "68") (name "Net-(E12A-Q5)") (class "Default")
      (node (ref "E12") (pin "12") (pinfunction "Q5_12") (pintype "output"))
      (node (ref "E17") (pin "12") (pinfunction "2C2_12") (pintype "input"))
    )
    (net (code "69") (name "Net-(E12A-Q6)") (class "Default")
      (node (ref "E12") (pin "15") (pinfunction "Q6_15") (pintype "output"))
      (node (ref "E17") (pin "10") (pinfunction "2C0_10") (pintype "input"))
    )
    (net (code "70") (name "Net-(E13A-Q1)") (class "Default")
      (node (ref "E13") (pin "2") (pinfunction "Q1_2") (pintype "output"))
      (node (ref "E19") (pin "12") (pinfunction "2C2_12") (pintype "input"))
    )
    (net (code "71") (name "Net-(E13A-Q2)") (class "Default")
      (node (ref "E13") (pin "5") (pinfunction "Q2_5") (pintype "output"))
      (node (ref "E19") (pin "10") (pinfunction "2C0_10") (pintype "input"))
    )
    (net (code "72") (name "Net-(E13A-Q3)") (class "Default")
      (node (ref "E13") (pin "7") (pinfunction "Q3_7") (pintype "output"))
      (node (ref "E18") (pin "3") (pinfunction "1C3_3") (pintype "input"))
    )
    (net (code "73") (name "Net-(E13A-Q4)") (class "Default")
      (node (ref "E13") (pin "10") (pinfunction "Q4_10") (pintype "output"))
      (node (ref "E18") (pin "5") (pinfunction "1C1_5") (pintype "input"))
    )
    (net (code "74") (name "Net-(E13A-Q5)") (class "Default")
      (node (ref "E13") (pin "12") (pinfunction "Q5_12") (pintype "output"))
      (node (ref "E18") (pin "4") (pinfunction "1C2_4") (pintype "input"))
    )
    (net (code "75") (name "Net-(E13A-Q6)") (class "Default")
      (node (ref "E13") (pin "15") (pinfunction "Q6_15") (pintype "output"))
      (node (ref "E18") (pin "6") (pinfunction "1C0_6") (pintype "input"))
    )
    (net (code "76") (name "Net-(E14A-Q1)") (class "Default")
      (node (ref "E14") (pin "2") (pinfunction "Q1_2") (pintype "output"))
      (node (ref "E18") (pin "13") (pinfunction "2C3_13") (pintype "input"))
    )
    (net (code "77") (name "Net-(E14A-Q2)") (class "Default")
      (node (ref "E14") (pin "5") (pinfunction "Q2_5") (pintype "output"))
      (node (ref "E18") (pin "11") (pinfunction "2C1_11") (pintype "input"))
    )
    (net (code "78") (name "Net-(E14A-Q3)") (class "Default")
      (node (ref "E14") (pin "7") (pinfunction "Q3_7") (pintype "output"))
      (node (ref "E18") (pin "12") (pinfunction "2C2_12") (pintype "input"))
    )
    (net (code "79") (name "Net-(E14A-Q4)") (class "Default")
      (node (ref "E14") (pin "10") (pinfunction "Q4_10") (pintype "output"))
      (node (ref "E18") (pin "10") (pinfunction "2C0_10") (pintype "input"))
    )
    (net (code "80") (name "Net-(E14A-Q5)") (class "Default")
      (node (ref "E14") (pin "12") (pinfunction "Q5_12") (pintype "output"))
      (node (ref "E17") (pin "3") (pinfunction "1C3_3") (pintype "input"))
    )
    (net (code "81") (name "Net-(E14A-Q6)") (class "Default")
      (node (ref "E14") (pin "15") (pinfunction "Q6_15") (pintype "output"))
      (node (ref "E17") (pin "5") (pinfunction "1C1_5") (pintype "input"))
    )
    (net (code "82") (name "Net-(E15A-Q1)") (class "Default")
      (node (ref "E15") (pin "2") (pinfunction "Q1_2") (pintype "output"))
      (node (ref "E19") (pin "3") (pinfunction "1C3_3") (pintype "input"))
    )
    (net (code "83") (name "Net-(E15A-Q2)") (class "Default")
      (node (ref "E15") (pin "5") (pinfunction "Q2_5") (pintype "output"))
      (node (ref "E19") (pin "5") (pinfunction "1C1_5") (pintype "input"))
    )
    (net (code "84") (name "Net-(E15A-Q3)") (class "Default")
      (node (ref "E15") (pin "7") (pinfunction "Q3_7") (pintype "output"))
      (node (ref "E19") (pin "4") (pinfunction "1C2_4") (pintype "input"))
    )
    (net (code "85") (name "Net-(E15A-Q4)") (class "Default")
      (node (ref "E15") (pin "10") (pinfunction "Q4_10") (pintype "output"))
      (node (ref "E19") (pin "6") (pinfunction "1C0_6") (pintype "input"))
    )
    (net (code "86") (name "Net-(E15A-Q5)") (class "Default")
      (node (ref "E15") (pin "12") (pinfunction "Q5_12") (pintype "output"))
      (node (ref "E19") (pin "13") (pinfunction "2C3_13") (pintype "input"))
    )
    (net (code "87") (name "Net-(E15A-Q6)") (class "Default")
      (node (ref "E15") (pin "15") (pinfunction "Q6_15") (pintype "output"))
      (node (ref "E19") (pin "11") (pinfunction "2C1_11") (pintype "input"))
    )
    (net (code "88") (name "Net-(E16A-CLK)") (class "Default")
      (node (ref "E16") (pin "3") (pinfunction "CLK_3") (pintype "input"))
      (node (ref "E21") (pin "12") (pinfunction "O_12") (pintype "output"))
    )
    (net (code "89") (name "Net-(E20A-PRE)") (class "Default")
      (node (ref "E20") (pin "4") (pinfunction "PRE_4") (pintype "input"))
      (node (ref "E26") (pin "8") (pinfunction "~{Q4}_8") (pintype "output"))
    )
    (net (code "90") (name "Net-(E20B-CLK)") (class "Default")
      (node (ref "E20") (pin "11") (pinfunction "CLK_11") (pintype "input"))
      (node (ref "E22") (pin "1") (pinfunction "O_1") (pintype "output"))
      (node (ref "E4") (pin "9") (pinfunction "A_9") (pintype "input"))
    )
    (net (code "91") (name "Net-(E21A-I0)") (class "Default")
      (node (ref "E21") (pin "1") (pinfunction "I0_1") (pintype "input"))
      (node (ref "E24") (pin "4") (pinfunction "O_4") (pintype "output"))
    )
    (net (code "92") (name "Net-(E21B-I0)") (class "Default")
      (node (ref "E21") (pin "3") (pinfunction "I0_3") (pintype "input"))
      (node (ref "E21") (pin "4") (pinfunction "I1_4") (pintype "input"))
      (node (ref "E22") (pin "4") (pinfunction "O_4") (pintype "output"))
    )
    (net (code "93") (name "Net-(E21C-O)") (class "Default")
      (node (ref "E21") (pin "8") (pinfunction "O_8") (pintype "output"))
      (node (ref "E23") (pin "9") (pinfunction "I_9") (pintype "input"))
    )
    (net (code "94") (name "Net-(E22A-I0)") (class "Default")
      (node (ref "E22") (pin "2") (pinfunction "I0_2") (pintype "input"))
      (node (ref "E32") (pin "6") (pinfunction "O_6") (pintype "output"))
    )
    (net (code "95") (name "Net-(E22A-I1)") (class "Default")
      (node (ref "E22") (pin "3") (pinfunction "I1_3") (pintype "input"))
      (node (ref "E33") (pin "1") (pinfunction "O_1") (pintype "output"))
    )
    (net (code "96") (name "Net-(E22B-I0)") (class "Default")
      (node (ref "E22") (pin "5") (pinfunction "I0_5") (pintype "input"))
      (node (ref "E8") (pin "3") (pinfunction "O_3") (pintype "output"))
    )
    (net (code "97") (name "Net-(E22C-I0)") (class "Default")
      (node (ref "E22") (pin "8") (pinfunction "I0_8") (pintype "input"))
      (node (ref "E25") (pin "12") (pinfunction "O_12") (pintype "output"))
    )
    (net (code "98") (name "Net-(E22C-I1)") (class "Default")
      (node (ref "E22") (pin "9") (pinfunction "I1_9") (pintype "input"))
      (node (ref "E25") (pin "8") (pinfunction "O_8") (pintype "output"))
    )
    (net (code "99") (name "Net-(E22C-O)") (class "Default")
      (node (ref "E22") (pin "10") (pinfunction "O_10") (pintype "output"))
      (node (ref "E29") (pin "4") (pinfunction "G2A_4") (pintype "input"))
      (node (ref "E29") (pin "5") (pinfunction "G2B_5") (pintype "input"))
      (node (ref "E31") (pin "15") (pinfunction "2G_15") (pintype "input"))
    )
    (net (code "100") (name "Net-(E22D-O)") (class "Default")
      (node (ref "E22") (pin "13") (pinfunction "O_13") (pintype "output"))
      (node (ref "E30") (pin "4") (pinfunction "I0_4") (pintype "input"))
    )
    (net (code "101") (name "Net-(E23A-I)") (class "Default")
      (node (ref "E23") (pin "1") (pinfunction "I_1") (pintype "input"))
      (node (ref "E33") (pin "4") (pinfunction "O_4") (pintype "output"))
    )
    (net (code "102") (name "Net-(E23E-I)") (class "Default")
      (node (ref "E23") (pin "11") (pinfunction "I_11") (pintype "input"))
      (node (ref "E24") (pin "10") (pinfunction "O_10") (pintype "output"))
    )
    (net (code "103") (name "Net-(E24D-O)") (class "Default")
      (node (ref "E24") (pin "8") (pinfunction "O_8") (pintype "output"))
      (node (ref "E32") (pin "5") (pinfunction "I1_5") (pintype "input"))
    )
    (net (code "104") (name "Net-(E24F-O)") (class "Default")
      (node (ref "E24") (pin "12") (pinfunction "O_12") (pintype "output"))
      (node (ref "E25") (pin "10") (pinfunction "I1_10") (pintype "input"))
      (node (ref "E28") (pin "1") (pinfunction "1G_1") (pintype "input"))
      (node (ref "E28") (pin "15") (pinfunction "2G_15") (pintype "input"))
      (node (ref "E33") (pin "6") (pinfunction "I1_6") (pintype "input"))
    )
    (net (code "105") (name "Net-(E25A-I0)") (class "Default")
      (node (ref "E25") (pin "1") (pinfunction "I0_1") (pintype "input"))
      (node (ref "E26") (pin "16") (pinfunction "Q1_16") (pintype "output"))
      (node (ref "E29") (pin "3") (pinfunction "C_3") (pintype "input"))
    )
    (net (code "106") (name "Net-(E25A-I2)") (class "Default")
      (node (ref "E25") (pin "13") (pinfunction "I2_13") (pintype "input"))
      (node (ref "E26") (pin "15") (pinfunction "Q2_15") (pintype "output"))
      (node (ref "E27") (pin "3") (pinfunction "I_3") (pintype "input"))
      (node (ref "E29") (pin "2") (pinfunction "B_2") (pintype "input"))
      (node (ref "E30") (pin "1") (pinfunction "I0_1") (pintype "input"))
    )
    (net (code "107") (name "Net-(E25C-I0)") (class "Default")
      (node (ref "E25") (pin "9") (pinfunction "I0_9") (pintype "input"))
      (node (ref "E26") (pin "9") (pinfunction "Q4_9") (pintype "output"))
    )
    (net (code "108") (name "Net-(E26A-Q3)") (class "Default")
      (node (ref "E26") (pin "10") (pinfunction "Q3_10") (pintype "output"))
      (node (ref "E29") (pin "1") (pinfunction "A_1") (pintype "input"))
    )
    (net (code "109") (name "Net-(E27A-O)") (class "Default")
      (node (ref "E27") (pin "2") (pinfunction "O_2") (pintype "output"))
      (node (ref "E30") (pin "12") (pinfunction "I0_12") (pintype "input"))
    )
    (net (code "110") (name "Net-(E27B-O)") (class "Default")
      (node (ref "E27") (pin "4") (pinfunction "O_4") (pintype "output"))
      (node (ref "E31") (pin "12") (pinfunction "2A1_12") (pintype "input"))
    )
    (net (code "111") (name "Net-(E27C-O)") (class "Default")
      (node (ref "E27") (pin "6") (pinfunction "O_6") (pintype "output"))
      (node (ref "E30") (pin "13") (pinfunction "I1_13") (pintype "input"))
    )
    (net (code "112") (name "Net-(E28A-1A1)") (class "Default")
      (node (ref "E28") (pin "2") (pinfunction "1A1_2") (pintype "input"))
      (node (ref "E29") (pin "9") (pinfunction "Y6_9") (pintype "output"))
      (node (ref "E32") (pin "2") (pinfunction "I1_2") (pintype "input"))
    )
    (net (code "113") (name "Net-(E28A-1A2)") (class "Default")
      (node (ref "E28") (pin "4") (pinfunction "1A2_4") (pintype "input"))
      (node (ref "E29") (pin "7") (pinfunction "Y7_7") (pintype "output"))
      (node (ref "E30") (pin "10") (pinfunction "I1_10") (pintype "input"))
      (node (ref "E32") (pin "1") (pinfunction "I0_1") (pintype "input"))
    )
    (net (code "114") (name "Net-(E28A-1A3)") (class "Default")
      (node (ref "E28") (pin "6") (pinfunction "1A3_6") (pintype "input"))
      (node (ref "E30") (pin "9") (pinfunction "I0_9") (pintype "input"))
      (node (ref "E31") (pin "6") (pinfunction "1A3_6") (pintype "input"))
      (node (ref "E32") (pin "8") (pinfunction "O_8") (pintype "output"))
      (node (ref "E33") (pin "5") (pinfunction "I0_5") (pintype "input"))
    )
    (net (code "115") (name "Net-(E28A-2A2)") (class "Default")
      (node (ref "E28") (pin "14") (pinfunction "2A2_14") (pintype "input"))
      (node (ref "E30") (pin "11") (pinfunction "O_11") (pintype "output"))
    )
    (net (code "116") (name "Net-(E29A-Y0)") (class "Default")
      (node (ref "E29") (pin "15") (pinfunction "Y0_15") (pintype "output"))
      (node (ref "E33") (pin "8") (pinfunction "I0_8") (pintype "input"))
    )
    (net (code "117") (name "Net-(E29A-Y1)") (class "Default")
      (node (ref "E29") (pin "14") (pinfunction "Y1_14") (pintype "output"))
      (node (ref "E33") (pin "12") (pinfunction "I1_12") (pintype "input"))
    )
    (net (code "118") (name "Net-(E29A-Y2)") (class "Default")
      (node (ref "E29") (pin "13") (pinfunction "Y2_13") (pintype "output"))
      (node (ref "E30") (pin "2") (pinfunction "I1_2") (pintype "input"))
      (node (ref "E32") (pin "10") (pinfunction "I1_10") (pintype "input"))
    )
    (net (code "119") (name "Net-(E29A-Y3)") (class "Default")
      (node (ref "E29") (pin "12") (pinfunction "Y3_12") (pintype "output"))
      (node (ref "E32") (pin "9") (pinfunction "I0_9") (pintype "input"))
    )
    (net (code "120") (name "Net-(E29A-Y4)") (class "Default")
      (node (ref "E29") (pin "11") (pinfunction "Y4_11") (pintype "output"))
      (node (ref "E31") (pin "10") (pinfunction "1A4_10") (pintype "input"))
    )
    (net (code "121") (name "Net-(E29A-Y5)") (class "Default")
      (node (ref "E29") (pin "10") (pinfunction "Y5_10") (pintype "output"))
      (node (ref "E31") (pin "2") (pinfunction "1A1_2") (pintype "input"))
    )
    (net (code "122") (name "Net-(E30A-O)") (class "Default")
      (node (ref "E30") (pin "3") (pinfunction "O_3") (pintype "output"))
      (node (ref "E31") (pin "14") (pinfunction "2A2_14") (pintype "input"))
    )
    (net (code "123") (name "Net-(E30B-O)") (class "Default")
      (node (ref "E30") (pin "6") (pinfunction "O_6") (pintype "output"))
      (node (ref "E34") (pin "1") (pinfunction "1G_1") (pintype "input"))
      (node (ref "E34") (pin "15") (pinfunction "2G_15") (pintype "input"))
      (node (ref "E35") (pin "4") (pinfunction "G2A_4") (pintype "input"))
      (node (ref "E35") (pin "5") (pinfunction "G2B_5") (pintype "input"))
    )
    (net (code "124") (name "Net-(E31A-1A2)") (class "Default")
      (node (ref "E31") (pin "4") (pinfunction "1A2_4") (pintype "input"))
      (node (ref "E32") (pin "3") (pinfunction "O_3") (pintype "output"))
    )
    (net (code "125") (name "Net-(E32D-I0)") (class "Default")
      (node (ref "E32") (pin "12") (pinfunction "I0_12") (pintype "input"))
      (node (ref "E35") (pin "11") (pinfunction "Y4_11") (pintype "output"))
    )
    (net (code "126") (name "Net-(E33C-O)") (class "Default")
      (node (ref "E33") (pin "10") (pinfunction "O_10") (pintype "output"))
      (node (ref "E36") (pin "9") (pinfunction "CLK_9") (pintype "input"))
    )
    (net (code "127") (name "Net-(E34A-1A3)") (class "Default")
      (node (ref "E34") (pin "6") (pinfunction "1A3_6") (pintype "input"))
      (node (ref "E35") (pin "9") (pinfunction "Y6_9") (pintype "output"))
    )
    (net (code "128") (name "Net-(E34A-2A1)") (class "Default")
      (node (ref "E34") (pin "12") (pinfunction "2A1_12") (pintype "input"))
      (node (ref "E35") (pin "10") (pinfunction "Y5_10") (pintype "output"))
    )
    (net (code "129") (name "POWCK") (class "Default")
      (node (ref "E24") (pin "11") (pinfunction "I_11") (pintype "input"))
      (node (ref "J2") (pin "28") (pinfunction "28_28") (pintype "passive"))
      (node (ref "R33") (pin "2") (pinfunction "2_2") (pintype "passive"))
    )
    (net (code "130") (name "THIS") (class "Default")
      (node (ref "E20") (pin "5") (pinfunction "Q_5") (pintype "output"))
      (node (ref "E28") (pin "12") (pinfunction "2A1_12") (pintype "input"))
    )
    (net (code "131") (name "VCC") (class "Default")
      (node (ref "C1") (pin "2") (pinfunction "2_2") (pintype "passive"))
      (node (ref "C10") (pin "2") (pinfunction "2_2") (pintype "passive"))
      (node (ref "C11") (pin "2") (pinfunction "2_2") (pintype "passive"))
      (node (ref "C12") (pin "2") (pinfunction "2_2") (pintype "passive"))
      (node (ref "C13") (pin "2") (pinfunction "2_2") (pintype "passive"))
      (node (ref "C14") (pin "2") (pinfunction "2_2") (pintype "passive"))
      (node (ref "C15") (pin "2") (pinfunction "2_2") (pintype "passive"))
      (node (ref "C16") (pin "2") (pinfunction "2_2") (pintype "passive"))
      (node (ref "C17") (pin "2") (pinfunction "2_2") (pintype "passive"))
      (node (ref "C18") (pin "2") (pinfunction "2_2") (pintype "passive"))
      (node (ref "C19") (pin "2") (pinfunction "2_2") (pintype "passive"))
      (node (ref "C2") (pin "2") (pinfunction "2_2") (pintype "passive"))
      (node (ref "C20") (pin "2") (pinfunction "2_2") (pintype "passive"))
      (node (ref "C21") (pin "2") (pinfunction "2_2") (pintype "passive"))
      (node (ref "C22") (pin "2") (pinfunction "2_2") (pintype "passive"))
      (node (ref "C23") (pin "2") (pinfunction "2_2") (pintype "passive"))
      (node (ref "C24") (pin "2") (pinfunction "2_2") (pintype "passive"))
      (node (ref "C25") (pin "2") (pinfunction "2_2") (pintype "passive"))
      (node (ref "C26") (pin "2") (pinfunction "2_2") (pintype "passive"))
      (node (ref "C27") (pin "2") (pinfunction "2_2") (pintype "passive"))
      (node (ref "C28") (pin "2") (pinfunction "2_2") (pintype "passive"))
      (node (ref "C29") (pin "2") (pinfunction "2_2") (pintype "passive"))
      (node (ref "C3") (pin "2") (pinfunction "2_2") (pintype "passive"))
      (node (ref "C30") (pin "2") (pinfunction "2_2") (pintype "passive"))
      (node (ref "C31") (pin "2") (pinfunction "2_2") (pintype "passive"))
      (node (ref "C32") (pin "2") (pinfunction "2_2") (pintype "passive"))
      (node (ref "C33") (pin "2") (pinfunction "2_2") (pintype "passive"))
      (node (ref "C34") (pin "2") (pinfunction "2_2") (pintype "passive"))
      (node (ref "C35") (pin "2") (pinfunction "2_2") (pintype "passive"))
      (node (ref "C36") (pin "2") (pinfunction "2_2") (pintype "passive"))
      (node (ref "C38") (pin "+") (pinfunction "+_+") (pintype "passive"))
      (node (ref "C39") (pin "+") (pinfunction "+_+") (pintype "passive"))
      (node (ref "C4") (pin "2") (pinfunction "2_2") (pintype "passive"))
      (node (ref "C5") (pin "2") (pinfunction "2_2") (pintype "passive"))
      (node (ref "C6") (pin "2") (pinfunction "2_2") (pintype "passive"))
      (node (ref "C7") (pin "2") (pinfunction "2_2") (pintype "passive"))
      (node (ref "C8") (pin "2") (pinfunction "2_2") (pintype "passive"))
      (node (ref "C9") (pin "2") (pinfunction "2_2") (pintype "passive"))
      (node (ref "E16") (pin "10") (pinfunction "PRE_10") (pintype "input"))
      (node (ref "E16") (pin "4") (pinfunction "PRE_4") (pintype "input"))
      (node (ref "E20") (pin "10") (pinfunction "PRE_10") (pintype "input"))
      (node (ref "E29") (pin "6") (pinfunction "G1_6") (pintype "input"))
      (node (ref "E34") (pin "10") (pinfunction "1A4_10") (pintype "input"))
      (node (ref "E35") (pin "6") (pinfunction "G1_6") (pintype "input"))
      (node (ref "E36") (pin "1") (pinfunction "CLR_1") (pintype "input"))
      (node (ref "E36") (pin "11") (pinfunction "D4_11") (pintype "input"))
      (node (ref "E36") (pin "13") (pinfunction "D5_13") (pintype "input"))
      (node (ref "E36") (pin "6") (pinfunction "D3_6") (pintype "input"))
      (node (ref "E4") (pin "10") (pinfunction "B_10") (pintype "input"))
      (node (ref "E4") (pin "11") (pinfunction "CLR_11") (pintype "input"))
      (node (ref "J1") (pin "1") (pinfunction "1_1") (pintype "passive"))
      (node (ref "J1") (pin "2") (pinfunction "2_2") (pintype "passive"))
      (node (ref "J1") (pin "3") (pinfunction "3_3") (pintype "passive"))
      (node (ref "J1") (pin "4") (pinfunction "4_4") (pintype "passive"))
      (node (ref "J1") (pin "5") (pinfunction "5_5") (pintype "passive"))
      (node (ref "J1") (pin "7") (pinfunction "7_7") (pintype "passive"))
      (node (ref "J1") (pin "9") (pinfunction "9_9") (pintype "passive"))
      (node (ref "J2") (pin "1") (pinfunction "1_1") (pintype "passive"))
      (node (ref "J2") (pin "3") (pinfunction "3_3") (pintype "passive"))
      (node (ref "J2") (pin "5") (pinfunction "5_5") (pintype "passive"))
      (node (ref "J2") (pin "7") (pinfunction "7_7") (pintype "passive"))
      (node (ref "J2") (pin "9") (pinfunction "9_9") (pintype "passive"))
      (node (ref "J3") (pin "16") (pinfunction "16_16") (pintype "passive"))
      (node (ref "J4") (pin "16") (pinfunction "16_16") (pintype "passive"))
      (node (ref "R10") (pin "2") (pinfunction "2_2") (pintype "passive"))
      (node (ref "R11") (pin "2") (pinfunction "2_2") (pintype "passive"))
      (node (ref "R12") (pin "2") (pinfunction "2_2") (pintype "passive"))
      (node (ref "R13") (pin "2") (pinfunction "2_2") (pintype "passive"))
      (node (ref "R14") (pin "2") (pinfunction "2_2") (pintype "passive"))
      (node (ref "R15") (pin "2") (pinfunction "2_2") (pintype "passive"))
      (node (ref "R16") (pin "2") (pinfunction "2_2") (pintype "passive"))
      (node (ref "R25") (pin "2") (pinfunction "2_2") (pintype "passive"))
      (node (ref "R26") (pin "1") (pinfunction "1_1") (pintype "passive"))
      (node (ref "R28") (pin "2") (pinfunction "2_2") (pintype "passive"))
      (node (ref "R29") (pin "1") (pinfunction "1_1") (pintype "passive"))
      (node (ref "R31") (pin "1") (pinfunction "1_1") (pintype "passive"))
      (node (ref "R32") (pin "1") (pinfunction "1_1") (pintype "passive"))
      (node (ref "R33") (pin "1") (pinfunction "1_1") (pintype "passive"))
      (node (ref "R34") (pin "1") (pinfunction "1_1") (pintype "passive"))
      (node (ref "R35") (pin "1") (pinfunction "1_1") (pintype "passive"))
      (node (ref "R36") (pin "1") (pinfunction "1_1") (pintype "passive"))
      (node (ref "R5") (pin "2") (pinfunction "2_2") (pintype "passive"))
      (node (ref "R6") (pin "2") (pinfunction "2_2") (pintype "passive"))
      (node (ref "R7") (pin "2") (pinfunction "2_2") (pintype "passive"))
      (node (ref "R8") (pin "2") (pinfunction "2_2") (pintype "passive"))
      (node (ref "R9") (pin "2") (pinfunction "2_2") (pintype "passive"))
      (node (ref "VCC") (pin "1") (pinfunction "P_1") (pintype "passive"))
    )
    (net (code "132") (name "unconnected-(D1-PadA)") (class "Default")
      (node (ref "D1") (pin "A") (pinfunction "A_A") (pintype "passive"))
    )
    (net (code "133") (name "unconnected-(D1-PadC)") (class "Default")
      (node (ref "D1") (pin "C") (pinfunction "C_C") (pintype "passive"))
    )
    (net (code "134") (name "unconnected-(D2-PadA)") (class "Default")
      (node (ref "D2") (pin "A") (pinfunction "A_A") (pintype "passive"))
    )
    (net (code "135") (name "unconnected-(D2-PadC)") (class "Default")
      (node (ref "D2") (pin "C") (pinfunction "C_C") (pintype "passive"))
    )
    (net (code "136") (name "unconnected-(E4B-~{Q}-Pad12)") (class "Default")
      (node (ref "E4") (pin "12") (pinfunction "~{Q}_12") (pintype "output"))
    )
    (net (code "137") (name "unconnected-(E5A-~{Q1}-Pad3)") (class "Default")
      (node (ref "E5") (pin "3") (pinfunction "~{Q1}_3") (pintype "output"))
    )
    (net (code "138") (name "unconnected-(E5A-~{Q2}-Pad6)") (class "Default")
      (node (ref "E5") (pin "6") (pinfunction "~{Q2}_6") (pintype "output"))
    )
    (net (code "139") (name "unconnected-(E5A-~{Q3}-Pad11)") (class "Default")
      (node (ref "E5") (pin "11") (pinfunction "~{Q3}_11") (pintype "output"))
    )
    (net (code "140") (name "unconnected-(E5A-~{Q4}-Pad14)") (class "Default")
      (node (ref "E5") (pin "14") (pinfunction "~{Q4}_14") (pintype "output"))
    )
    (net (code "141") (name "unconnected-(E6A-~{Q1}-Pad3)") (class "Default")
      (node (ref "E6") (pin "3") (pinfunction "~{Q1}_3") (pintype "output"))
    )
    (net (code "142") (name "unconnected-(E6A-~{Q2}-Pad6)") (class "Default")
      (node (ref "E6") (pin "6") (pinfunction "~{Q2}_6") (pintype "output"))
    )
    (net (code "143") (name "unconnected-(E6A-~{Q3}-Pad11)") (class "Default")
      (node (ref "E6") (pin "11") (pinfunction "~{Q3}_11") (pintype "output"))
    )
    (net (code "144") (name "unconnected-(E6A-~{Q4}-Pad14)") (class "Default")
      (node (ref "E6") (pin "14") (pinfunction "~{Q4}_14") (pintype "output"))
    )
    (net (code "145") (name "unconnected-(E7A-~{Q1}-Pad3)") (class "Default")
      (node (ref "E7") (pin "3") (pinfunction "~{Q1}_3") (pintype "output"))
    )
    (net (code "146") (name "unconnected-(E7A-~{Q2}-Pad6)") (class "Default")
      (node (ref "E7") (pin "6") (pinfunction "~{Q2}_6") (pintype "output"))
    )
    (net (code "147") (name "unconnected-(E7A-~{Q3}-Pad11)") (class "Default")
      (node (ref "E7") (pin "11") (pinfunction "~{Q3}_11") (pintype "output"))
    )
    (net (code "148") (name "unconnected-(E7A-~{Q4}-Pad14)") (class "Default")
      (node (ref "E7") (pin "14") (pinfunction "~{Q4}_14") (pintype "output"))
    )
    (net (code "149") (name "unconnected-(E16A-Q-Pad5)") (class "Default")
      (node (ref "E16") (pin "5") (pinfunction "Q_5") (pintype "output"))
    )
    (net (code "150") (name "unconnected-(E20A-~{Q}-Pad6)") (class "Default")
      (node (ref "E20") (pin "6") (pinfunction "~{Q}_6") (pintype "output"))
    )
    (net (code "151") (name "unconnected-(E26A-~{Q1}-Pad1)") (class "Default")
      (node (ref "E26") (pin "1") (pinfunction "~{Q1}_1") (pintype "output"))
    )
    (net (code "152") (name "unconnected-(E26A-~{Q2}-Pad14)") (class "Default")
      (node (ref "E26") (pin "14") (pinfunction "~{Q2}_14") (pintype "output"))
    )
    (net (code "153") (name "unconnected-(E26A-~{Q3}-Pad11)") (class "Default")
      (node (ref "E26") (pin "11") (pinfunction "~{Q3}_11") (pintype "output"))
    )
    (net (code "154") (name "unconnected-(E34A-1Y4-Pad9)") (class "Default")
      (node (ref "E34") (pin "9") (pinfunction "1Y4_9") (pintype "tri_state"))
    )
    (net (code "155") (name "unconnected-(E35A-Y0-Pad15)") (class "Default")
      (node (ref "E35") (pin "15") (pinfunction "Y0_15") (pintype "output"))
    )
    (net (code "156") (name "unconnected-(E35A-Y1-Pad14)") (class "Default")
      (node (ref "E35") (pin "14") (pinfunction "Y1_14") (pintype "output"))
    )
    (net (code "157") (name "unconnected-(E35A-Y2-Pad13)") (class "Default")
      (node (ref "E35") (pin "13") (pinfunction "Y2_13") (pintype "output"))
    )
    (net (code "158") (name "unconnected-(E35A-Y3-Pad12)") (class "Default")
      (node (ref "E35") (pin "12") (pinfunction "Y3_12") (pintype "output"))
    )
    (net (code "159") (name "unconnected-(E35A-Y7-Pad7)") (class "Default")
      (node (ref "E35") (pin "7") (pinfunction "Y7_7") (pintype "output"))
    )
    (net (code "160") (name "unconnected-(E36A-Q3-Pad7)") (class "Default")
      (node (ref "E36") (pin "7") (pinfunction "Q3_7") (pintype "output"))
    )
    (net (code "161") (name "unconnected-(E36A-Q4-Pad10)") (class "Default")
      (node (ref "E36") (pin "10") (pinfunction "Q4_10") (pintype "output"))
    )
    (net (code "162") (name "unconnected-(E36A-Q5-Pad12)") (class "Default")
      (node (ref "E36") (pin "12") (pinfunction "Q5_12") (pintype "output"))
    )
    (net (code "163") (name "~{ADRLTH}") (class "Default")
      (node (ref "E12") (pin "9") (pinfunction "CLK_9") (pintype "input"))
      (node (ref "E14") (pin "9") (pinfunction "CLK_9") (pintype "input"))
      (node (ref "E8") (pin "11") (pinfunction "O_11") (pintype "output"))
    )
    (net (code "164") (name "~{BFSW}") (class "Default")
      (node (ref "E28") (pin "9") (pinfunction "1Y4_9") (pintype "tri_state"))
      (node (ref "J2") (pin "24") (pinfunction "24_24") (pintype "passive"))
    )
    (net (code "165") (name "~{BKDTACNTL}") (class "Default")
      (node (ref "E28") (pin "3") (pinfunction "1Y1_3") (pintype "tri_state"))
      (node (ref "J2") (pin "12") (pinfunction "12_12") (pintype "passive"))
    )
    (net (code "166") (name "~{BOOTF}") (class "Default")
      (node (ref "E16") (pin "2") (pinfunction "D_2") (pintype "input"))
      (node (ref "E16") (pin "6") (pinfunction "~{Q}_6") (pintype "output"))
      (node (ref "E28") (pin "10") (pinfunction "1A4_10") (pintype "input"))
    )
    (net (code "167") (name "~{BUSEN}") (class "Default")
      (node (ref "E34") (pin "13") (pinfunction "2Y2_13") (pintype "tri_state"))
      (node (ref "J1") (pin "24") (pinfunction "24_24") (pintype "passive"))
    )
    (net (code "168") (name "~{DEP}") (class "Default")
      (node (ref "E28") (pin "5") (pinfunction "1Y2_5") (pintype "tri_state"))
      (node (ref "J2") (pin "20") (pinfunction "20_20") (pintype "passive"))
    )
    (net (code "169") (name "~{DSPLTH}") (class "Default")
      (node (ref "E13") (pin "9") (pinfunction "CLK_9") (pintype "input"))
      (node (ref "E15") (pin "9") (pinfunction "CLK_9") (pintype "input"))
      (node (ref "E8") (pin "8") (pinfunction "O_8") (pintype "output"))
    )
    (net (code "170") (name "~{EMA0}") (class "Default")
      (node (ref "E27") (pin "11") (pinfunction "I_11") (pintype "input"))
      (node (ref "J1") (pin "30") (pinfunction "30_30") (pintype "passive"))
      (node (ref "R34") (pin "2") (pinfunction "2_2") (pintype "passive"))
    )
    (net (code "171") (name "~{EMA1}") (class "Default")
      (node (ref "E27") (pin "9") (pinfunction "I_9") (pintype "input"))
      (node (ref "J1") (pin "28") (pinfunction "28_28") (pintype "passive"))
      (node (ref "R35") (pin "2") (pinfunction "2_2") (pintype "passive"))
    )
    (net (code "172") (name "~{EMA2}") (class "Default")
      (node (ref "E27") (pin "13") (pinfunction "I_13") (pintype "input"))
      (node (ref "J1") (pin "32") (pinfunction "32_32") (pintype "passive"))
      (node (ref "R36") (pin "2") (pinfunction "2_2") (pintype "passive"))
    )
    (net (code "173") (name "~{EMODE}") (class "Default")
      (node (ref "E1") (pin "6") (pinfunction "MOD_6") (pintype "input"))
      (node (ref "E16") (pin "8") (pinfunction "~{Q}_8") (pintype "output"))
      (node (ref "E2") (pin "6") (pinfunction "MOD_6") (pintype "input"))
      (node (ref "E22") (pin "6") (pinfunction "I1_6") (pintype "input"))
      (node (ref "E3") (pin "6") (pinfunction "MOD_6") (pintype "input"))
    )
    (net (code "174") (name "~{EXTPUL}") (class "Default")
      (node (ref "J4") (pin "9") (pinfunction "9_9") (pintype "passive"))
    )
    (net (code "175") (name "~{FUN}") (class "Default")
      (node (ref "E24") (pin "3") (pinfunction "I_3") (pintype "input"))
      (node (ref "E25") (pin "11") (pinfunction "I2_11") (pintype "input"))
      (node (ref "E25") (pin "2") (pinfunction "I1_2") (pintype "input"))
      (node (ref "J4") (pin "15") (pinfunction "15_15") (pintype "passive"))
    )
    (net (code "176") (name "~{GATEENT}") (class "Default")
      (node (ref "E10") (pin "1") (pinfunction "G_1") (pintype "input"))
      (node (ref "E11") (pin "1") (pinfunction "G_1") (pintype "input"))
      (node (ref "E21") (pin "6") (pinfunction "O_6") (pintype "output"))
      (node (ref "E30") (pin "5") (pinfunction "I1_5") (pintype "input"))
      (node (ref "E9") (pin "1") (pinfunction "G_1") (pintype "input"))
    )
    (net (code "177") (name "~{GATESR}") (class "Default")
      (node (ref "E10") (pin "19") (pinfunction "G_19") (pintype "input"))
      (node (ref "E11") (pin "19") (pinfunction "G_19") (pintype "input"))
      (node (ref "E32") (pin "11") (pinfunction "O_11") (pintype "output"))
      (node (ref "E9") (pin "19") (pinfunction "G_19") (pintype "input"))
    )
    (net (code "178") (name "~{IND1}") (class "Default")
      (node (ref "E28") (pin "7") (pinfunction "1Y3_7") (pintype "tri_state"))
      (node (ref "E34") (pin "3") (pinfunction "1Y1_3") (pintype "tri_state"))
      (node (ref "J2") (pin "8") (pinfunction "8_8") (pintype "passive"))
    )
    (net (code "179") (name "~{IND2}") (class "Default")
      (node (ref "E34") (pin "5") (pinfunction "1Y2_5") (pintype "tri_state"))
      (node (ref "J2") (pin "4") (pinfunction "4_4") (pintype "passive"))
    )
    (net (code "180") (name "~{INIT}") (class "Default")
      (node (ref "E31") (pin "9") (pinfunction "1Y4_9") (pintype "tri_state"))
      (node (ref "J2") (pin "34") (pinfunction "34_34") (pintype "passive"))
    )
    (net (code "181") (name "~{KEY-F}") (class "Default")
      (node (ref "E26") (pin "13") (pinfunction "C12_13") (pintype "input"))
      (node (ref "E26") (pin "4") (pinfunction "C34_4") (pintype "input"))
      (node (ref "E27") (pin "5") (pinfunction "I_5") (pintype "input"))
      (node (ref "J4") (pin "3") (pinfunction "3_3") (pintype "passive"))
    )
    (net (code "182") (name "~{KEYCNTL}") (class "Default")
      (node (ref "E31") (pin "13") (pinfunction "2Y2_13") (pintype "tri_state"))
      (node (ref "J2") (pin "10") (pinfunction "10_10") (pintype "passive"))
    )
    (net (code "183") (name "~{KEYSTB}") (class "Default")
      (node (ref "E16") (pin "11") (pinfunction "CLK_11") (pintype "input"))
      (node (ref "E21") (pin "2") (pinfunction "I1_2") (pintype "input"))
      (node (ref "E24") (pin "2") (pinfunction "O_2") (pintype "output"))
      (node (ref "E31") (pin "1") (pinfunction "1G_1") (pintype "input"))
      (node (ref "E33") (pin "11") (pinfunction "I0_11") (pintype "input"))
      (node (ref "E33") (pin "9") (pinfunction "I1_9") (pintype "input"))
    )
    (net (code "184") (name "~{KFUN0}") (class "Default")
      (node (ref "E26") (pin "2") (pinfunction "D1_2") (pintype "input"))
      (node (ref "E3") (pin "1") (pinfunction "SER_1") (pintype "input"))
      (node (ref "E3") (pin "2") (pinfunction "A_2") (pintype "input"))
      (node (ref "J3") (pin "3") (pinfunction "3_3") (pintype "passive"))
    )
    (net (code "185") (name "~{KFUN1}") (class "Default")
      (node (ref "E2") (pin "1") (pinfunction "SER_1") (pintype "input"))
      (node (ref "E2") (pin "2") (pinfunction "A_2") (pintype "input"))
      (node (ref "E26") (pin "3") (pinfunction "D2_3") (pintype "input"))
      (node (ref "J3") (pin "2") (pinfunction "2_2") (pintype "passive"))
    )
    (net (code "186") (name "~{KFUN2}") (class "Default")
      (node (ref "E1") (pin "1") (pinfunction "SER_1") (pintype "input"))
      (node (ref "E1") (pin "2") (pinfunction "A_2") (pintype "input"))
      (node (ref "E26") (pin "6") (pinfunction "D3_6") (pintype "input"))
      (node (ref "J3") (pin "1") (pinfunction "1_1") (pintype "passive"))
    )
    (net (code "187") (name "~{LAENAB}") (class "Default")
      (node (ref "E23") (pin "2") (pinfunction "O_2") (pintype "open_collector"))
      (node (ref "J2") (pin "22") (pinfunction "22_22") (pintype "passive"))
    )
    (net (code "188") (name "~{MAEN}") (class "Default")
      (node (ref "E23") (pin "8") (pinfunction "O_8") (pintype "open_collector"))
      (node (ref "J2") (pin "32") (pinfunction "32_32") (pintype "passive"))
    )
    (net (code "189") (name "~{MALC}") (class "Default")
      (node (ref "E28") (pin "11") (pinfunction "2Y1_11") (pintype "tri_state"))
      (node (ref "J2") (pin "36") (pinfunction "36_36") (pintype "passive"))
    )
    (net (code "190") (name "~{MCLOCK}") (class "Default")
      (node (ref "E33") (pin "2") (pinfunction "I0_2") (pintype "input"))
      (node (ref "J4") (pin "1") (pinfunction "1_1") (pintype "passive"))
    )
    (net (code "191") (name "~{MD}") (class "Default")
      (node (ref "E34") (pin "7") (pinfunction "1Y3_7") (pintype "tri_state"))
      (node (ref "J2") (pin "18") (pinfunction "18_18") (pintype "passive"))
    )
    (net (code "192") (name "~{MEMSTART}") (class "Default")
      (node (ref "E31") (pin "3") (pinfunction "1Y1_3") (pintype "tri_state"))
      (node (ref "E31") (pin "5") (pinfunction "1Y2_5") (pintype "tri_state"))
      (node (ref "J2") (pin "26") (pinfunction "26_26") (pintype "passive"))
    )
    (net (code "193") (name "~{MH0}") (class "Default")
      (node (ref "E20") (pin "12") (pinfunction "D_12") (pintype "input"))
      (node (ref "E20") (pin "8") (pinfunction "~{Q}_8") (pintype "output"))
      (node (ref "E21") (pin "9") (pinfunction "I0_9") (pintype "input"))
      (node (ref "E8") (pin "2") (pinfunction "I1_2") (pintype "input"))
      (node (ref "E8") (pin "9") (pinfunction "I0_9") (pintype "input"))
    )
    (net (code "194") (name "~{MSIRDIS}") (class "Default")
      (node (ref "E31") (pin "11") (pinfunction "2Y1_11") (pintype "tri_state"))
      (node (ref "J2") (pin "2") (pinfunction "2_2") (pintype "passive"))
    )
    (net (code "195") (name "~{PANLOCK}") (class "Default")
      (node (ref "E24") (pin "13") (pinfunction "I_13") (pintype "input"))
      (node (ref "J2") (pin "6") (pinfunction "6_6") (pintype "passive"))
      (node (ref "R31") (pin "2") (pinfunction "2_2") (pintype "passive"))
    )
    (net (code "196") (name "~{PULSELOADADD}") (class "Default")
      (node (ref "E31") (pin "7") (pinfunction "1Y3_7") (pintype "tri_state"))
      (node (ref "J2") (pin "40") (pinfunction "40_40") (pintype "passive"))
    )
    (net (code "197") (name "~{RUN}") (class "Default")
      (node (ref "E24") (pin "5") (pinfunction "I_5") (pintype "input"))
      (node (ref "J1") (pin "18") (pinfunction "18_18") (pintype "passive"))
      (node (ref "R28") (pin "1") (pinfunction "1_1") (pintype "passive"))
    )
    (net (code "198") (name "~{SHLT}") (class "Default")
      (node (ref "E27") (pin "1") (pinfunction "I_1") (pintype "input"))
      (node (ref "J3") (pin "5") (pinfunction "5_5") (pintype "passive"))
    )
    (net (code "199") (name "~{SINGSTEP}") (class "Default")
      (node (ref "E28") (pin "13") (pinfunction "2Y2_13") (pintype "tri_state"))
      (node (ref "J2") (pin "14") (pinfunction "14_14") (pintype "passive"))
    )
    (net (code "200") (name "~{SRDATA}") (class "Default")
      (node (ref "E32") (pin "13") (pinfunction "I1_13") (pintype "input"))
      (node (ref "E8") (pin "1") (pinfunction "I0_1") (pintype "input"))
      (node (ref "J2") (pin "30") (pinfunction "30_30") (pintype "passive"))
      (node (ref "R29") (pin "2") (pinfunction "2_2") (pintype "passive"))
      (node (ref "R30") (pin "1") (pinfunction "1_1") (pintype "passive"))
    )
    (net (code "201") (name "~{STATE}") (class "Default")
      (node (ref "E34") (pin "11") (pinfunction "2Y1_11") (pintype "tri_state"))
      (node (ref "J2") (pin "38") (pinfunction "38_38") (pintype "passive"))
    )
    (net (code "202") (name "~{STHIS}") (class "Default")
      (node (ref "E20") (pin "2") (pinfunction "D_2") (pintype "input"))
      (node (ref "J3") (pin "4") (pinfunction "4_4") (pintype "passive"))
    )
    (net (code "203") (name "~{TS1}") (class "Default")
      (node (ref "E20") (pin "3") (pinfunction "CLK_3") (pintype "input"))
      (node (ref "E21") (pin "10") (pinfunction "I1_10") (pintype "input"))
      (node (ref "E24") (pin "9") (pinfunction "I_9") (pintype "input"))
      (node (ref "J1") (pin "26") (pinfunction "26_26") (pintype "passive"))
      (node (ref "R26") (pin "2") (pinfunction "2_2") (pintype "passive"))
      (node (ref "R27") (pin "1") (pinfunction "1_1") (pintype "passive"))
    )
  )
)
